# EEG_64.net
KiCad netlist of a schematic drawn in EAGLE
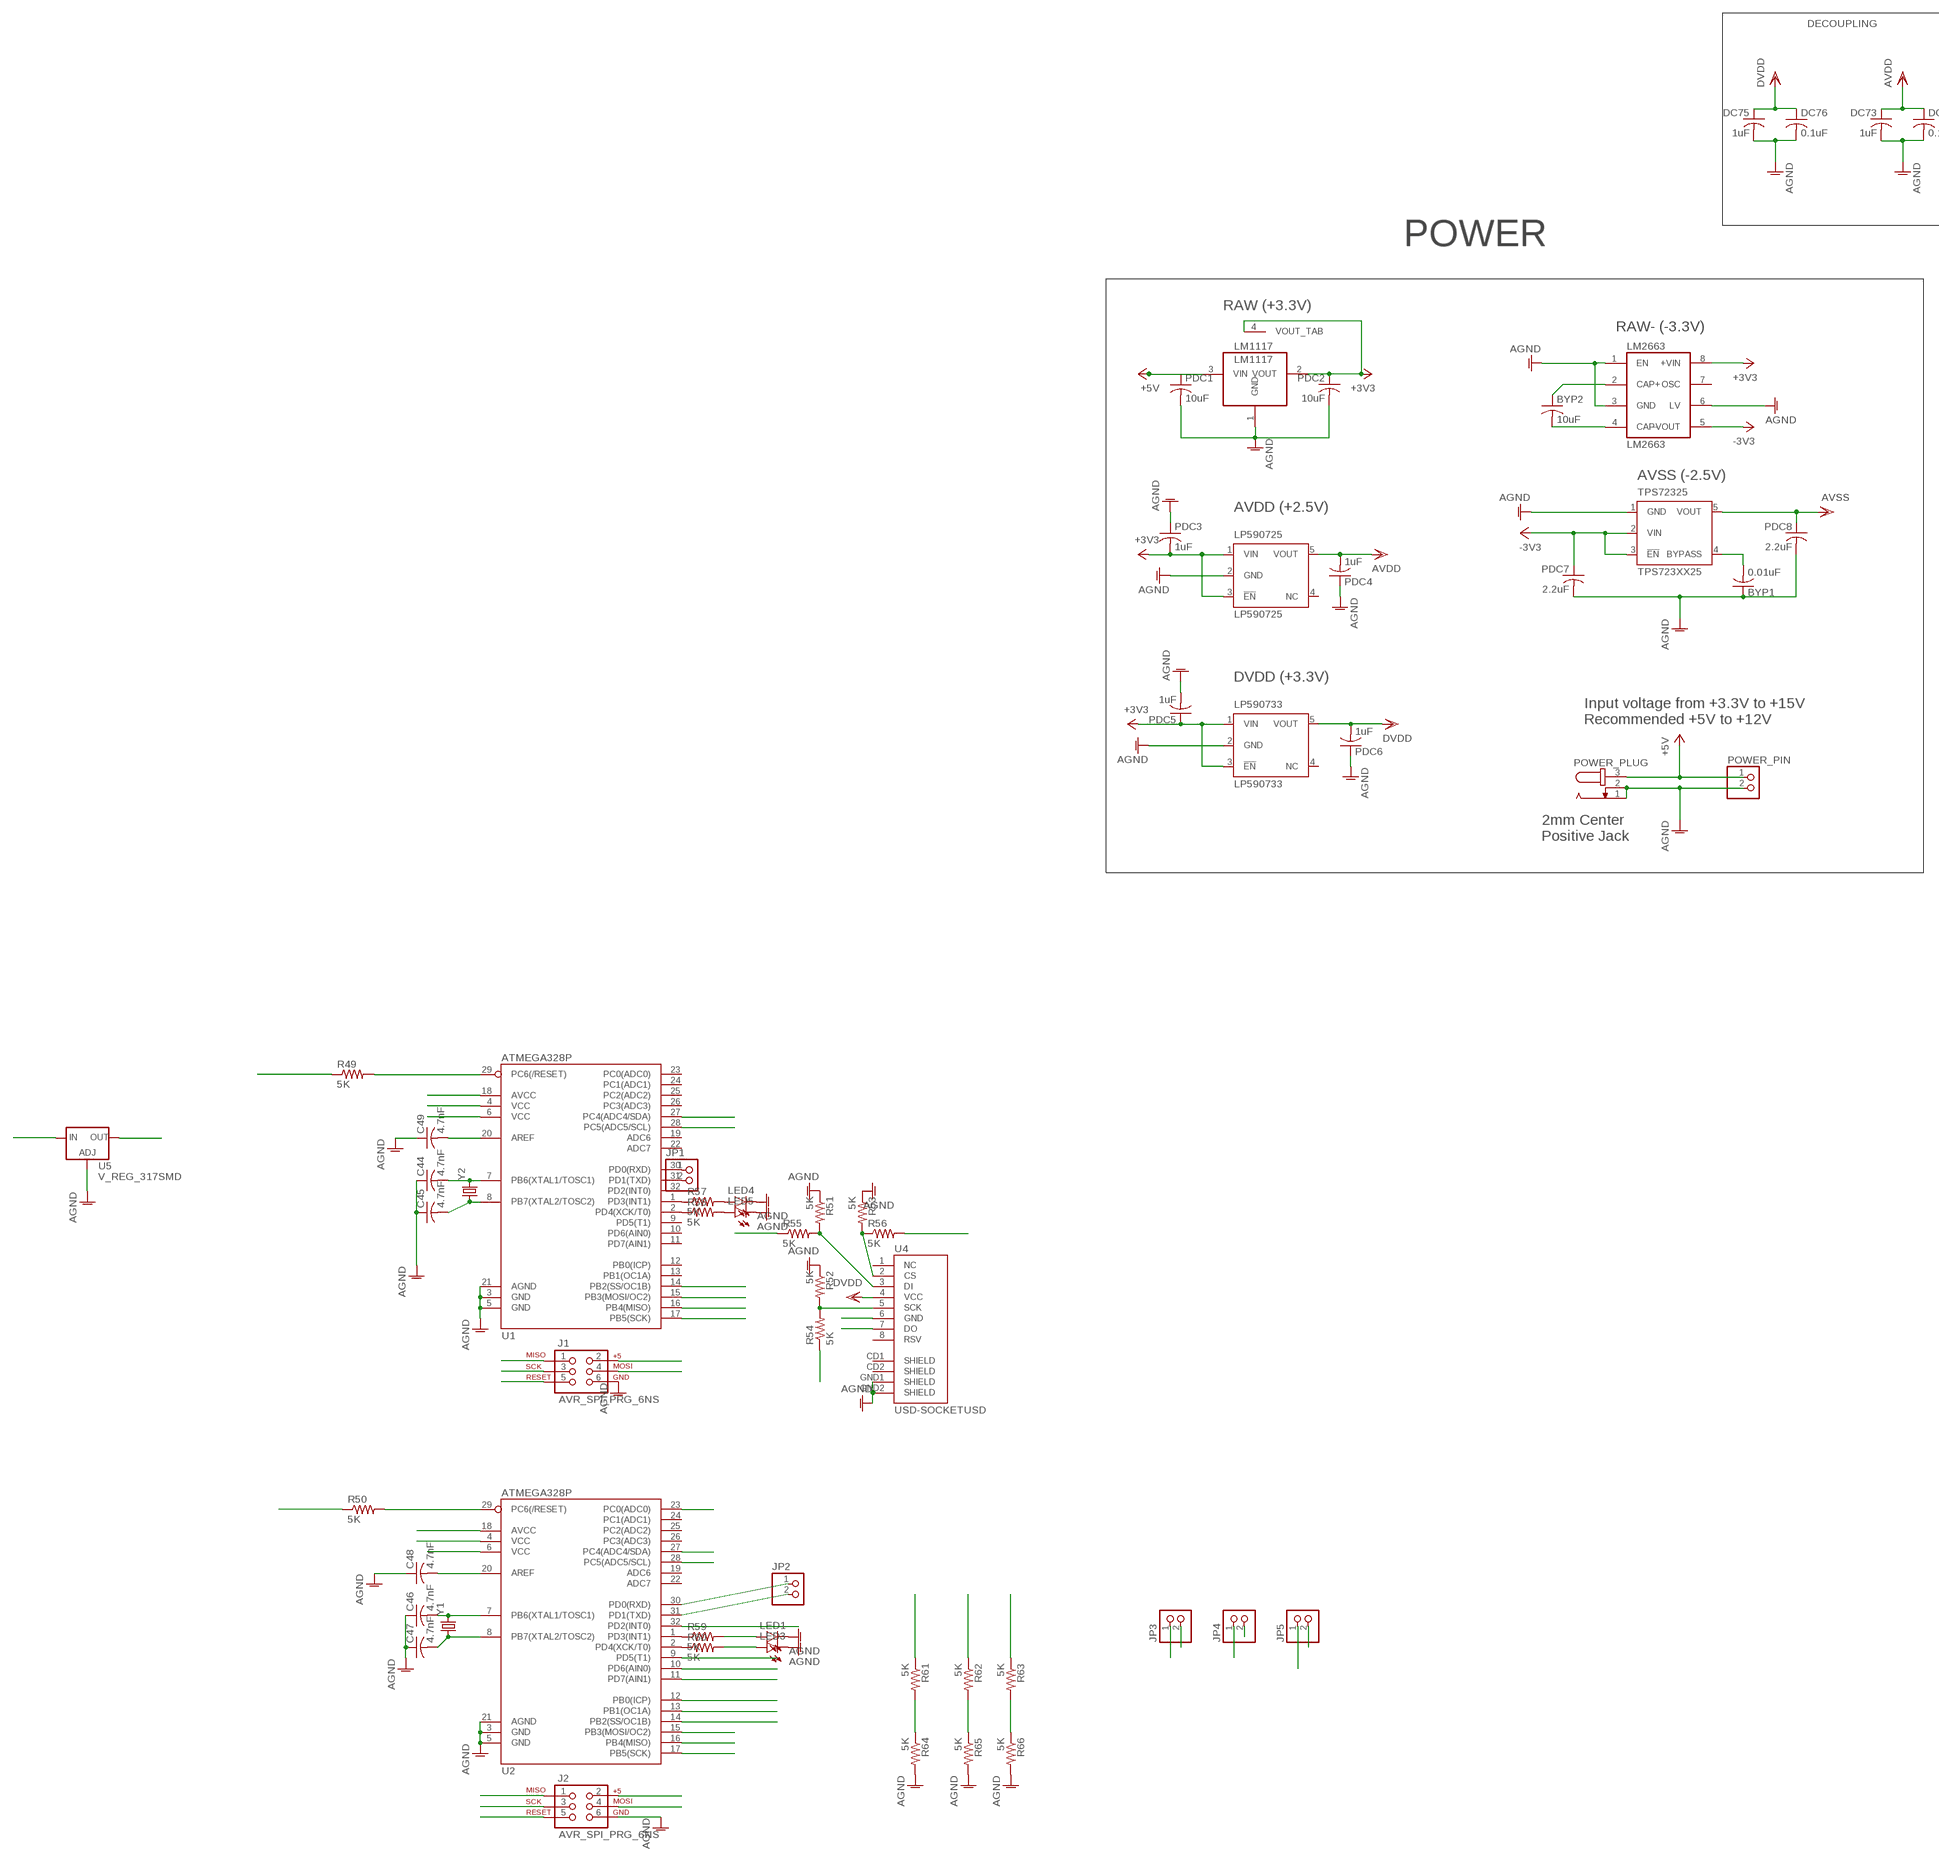
[diagram p0: schematic, sheet 1, part 1 of 3]
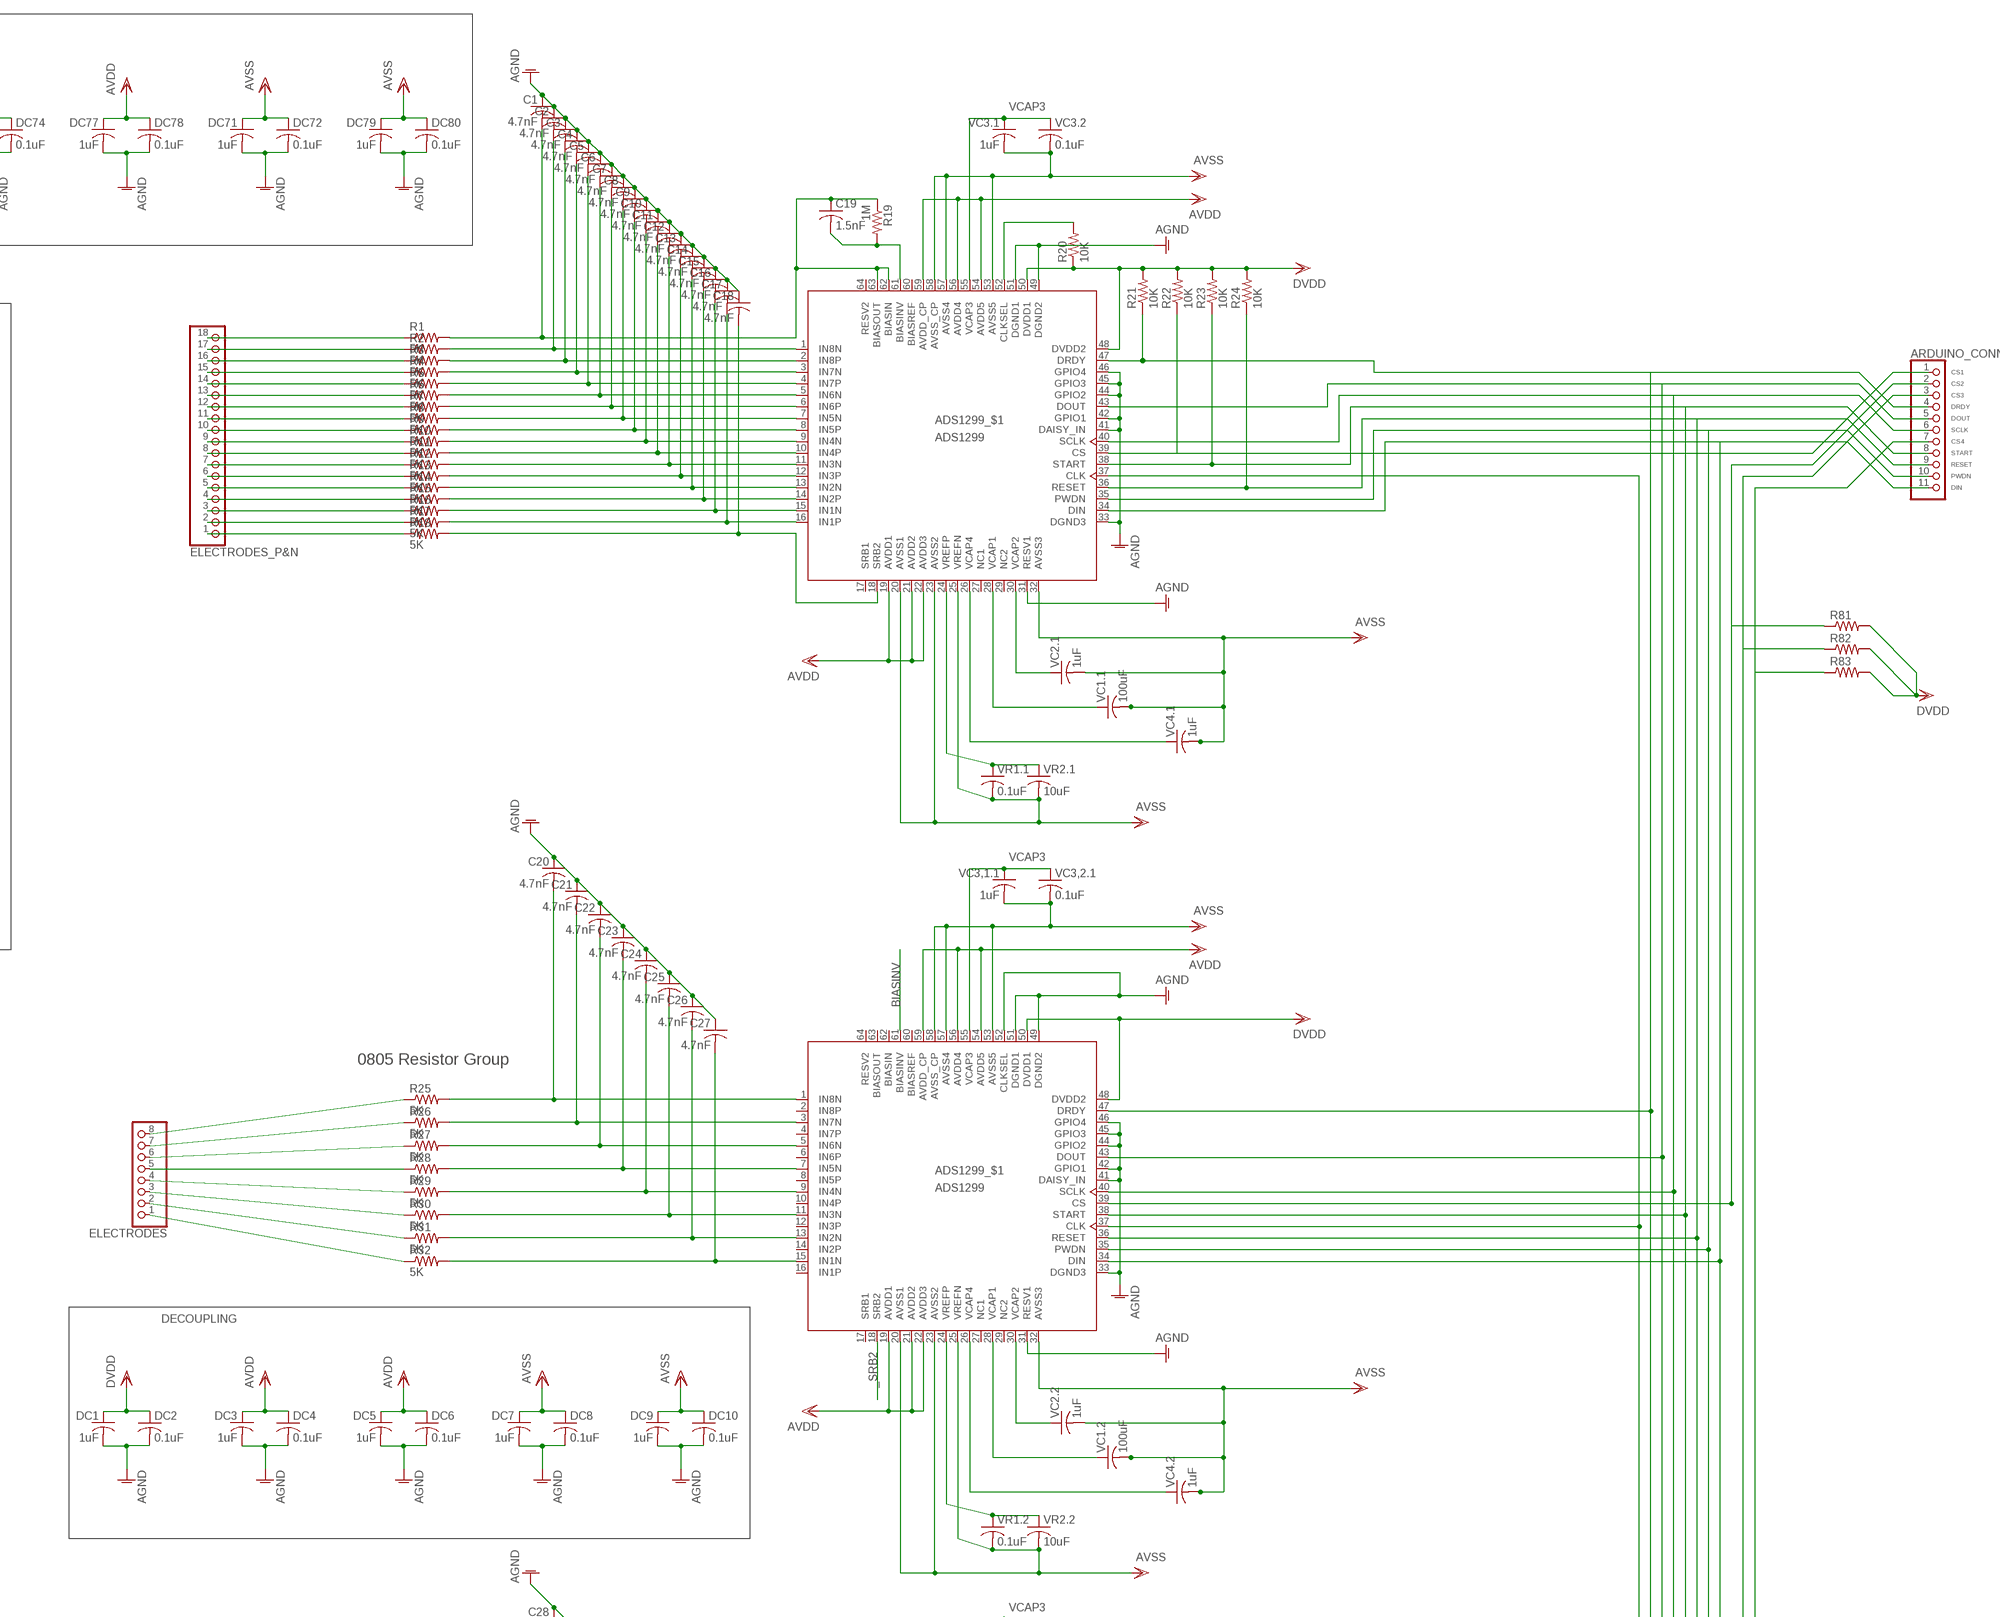
[diagram p1: schematic, sheet 1, part 2 of 3]
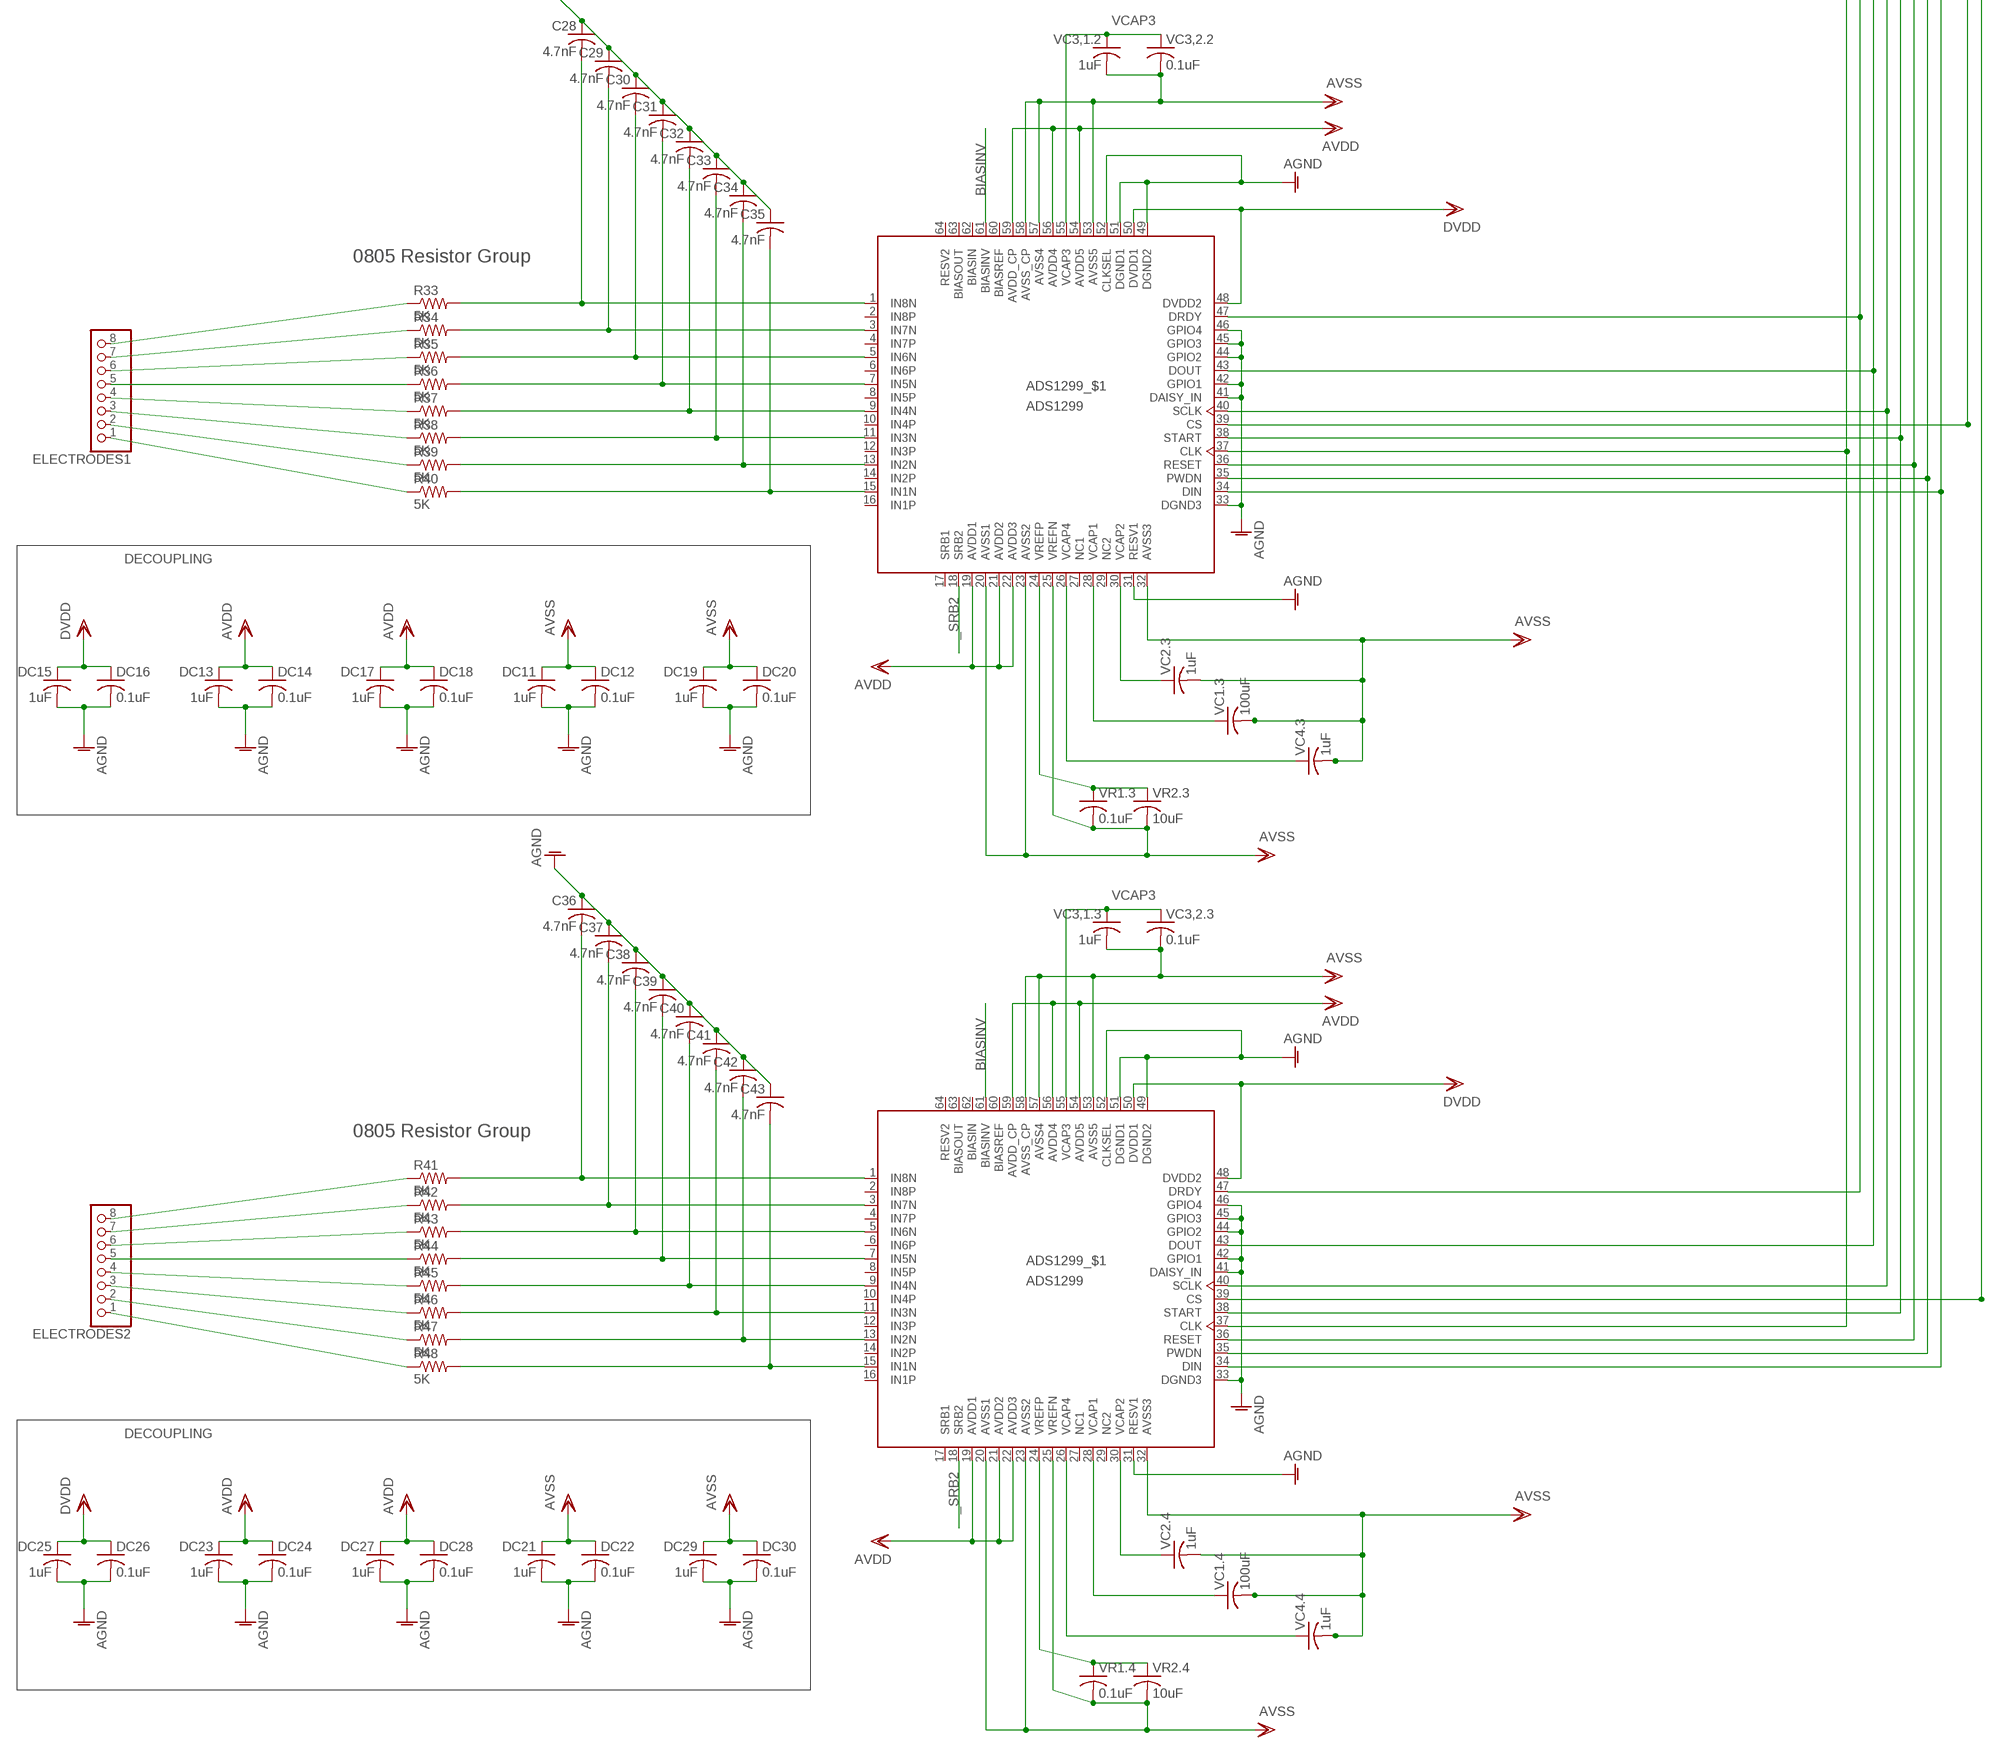
[diagram p2: schematic, sheet 1, part 3 of 3]

(export (version "E")
  (design (tool "Eeschema 10.0.6"))
  (components
    (comp (ref "ADS1")
      (value "ADS1299")
      (footprint "eagle-import:PAG_S-PQFP-G64")
      (fields (field (name "MF") "TEXAS INSTRUMENTS") (field (name "MPN") "ADS1299PAGR"))
      (libsource (lib "eagle-import") (part "ADS1299"))
    )
    (comp (ref "ADS2")
      (value "ADS1299")
      (footprint "eagle-import:PAG_S-PQFP-G64")
      (fields (field (name "MF") "TEXAS INSTRUMENTS") (field (name "MPN") "ADS1299PAGR"))
      (libsource (lib "eagle-import") (part "ADS1299"))
    )
    (comp (ref "ADS3")
      (value "ADS1299")
      (footprint "eagle-import:PAG_S-PQFP-G64")
      (fields (field (name "MF") "TEXAS INSTRUMENTS") (field (name "MPN") "ADS1299PAGR"))
      (libsource (lib "eagle-import") (part "ADS1299"))
    )
    (comp (ref "ADS4")
      (value "ADS1299")
      (footprint "eagle-import:PAG_S-PQFP-G64")
      (fields (field (name "MF") "TEXAS INSTRUMENTS") (field (name "MPN") "ADS1299PAGR"))
      (libsource (lib "eagle-import") (part "ADS1299"))
    )
    (comp (ref "ARDUINO_CONN")
      (value "PINHD-1X11")
      (footprint "eagle-import:1X11")
      (libsource (lib "eagle-import") (part "PINHD-1X11"))
    )
    (comp (ref "BYP1")
      (value "0.01uF")
      (footprint "eagle-import:C0603")
      (libsource (lib "eagle-import") (part "resistor_C-USC0603"))
    )
    (comp (ref "BYP2")
      (value "10uF")
      (footprint "eagle-import:C0603")
      (libsource (lib "eagle-import") (part "resistor_C-USC0603"))
    )
    (comp (ref "C1")
      (value "4.7nF")
      (footprint "eagle-import:C0603")
      (libsource (lib "eagle-import") (part "resistor_C-USC0603"))
    )
    (comp (ref "C2")
      (value "4.7nF")
      (footprint "eagle-import:C0603")
      (libsource (lib "eagle-import") (part "resistor_C-USC0603"))
    )
    (comp (ref "C3")
      (value "4.7nF")
      (footprint "eagle-import:C0603")
      (libsource (lib "eagle-import") (part "resistor_C-USC0603"))
    )
    (comp (ref "C4")
      (value "4.7nF")
      (footprint "eagle-import:C0603")
      (libsource (lib "eagle-import") (part "resistor_C-USC0603"))
    )
    (comp (ref "C5")
      (value "4.7nF")
      (footprint "eagle-import:C0603")
      (libsource (lib "eagle-import") (part "resistor_C-USC0603"))
    )
    (comp (ref "C6")
      (value "4.7nF")
      (footprint "eagle-import:C0603")
      (libsource (lib "eagle-import") (part "resistor_C-USC0603"))
    )
    (comp (ref "C7")
      (value "4.7nF")
      (footprint "eagle-import:C0603")
      (libsource (lib "eagle-import") (part "resistor_C-USC0603"))
    )
    (comp (ref "C8")
      (value "4.7nF")
      (footprint "eagle-import:C0603")
      (libsource (lib "eagle-import") (part "resistor_C-USC0603"))
    )
    (comp (ref "C9")
      (value "4.7nF")
      (footprint "eagle-import:C0603")
      (libsource (lib "eagle-import") (part "resistor_C-USC0603"))
    )
    (comp (ref "C10")
      (value "4.7nF")
      (footprint "eagle-import:C0603")
      (libsource (lib "eagle-import") (part "resistor_C-USC0603"))
    )
    (comp (ref "C11")
      (value "4.7nF")
      (footprint "eagle-import:C0603")
      (libsource (lib "eagle-import") (part "resistor_C-USC0603"))
    )
    (comp (ref "C12")
      (value "4.7nF")
      (footprint "eagle-import:C0603")
      (libsource (lib "eagle-import") (part "resistor_C-USC0603"))
    )
    (comp (ref "C13")
      (value "4.7nF")
      (footprint "eagle-import:C0603")
      (libsource (lib "eagle-import") (part "resistor_C-USC0603"))
    )
    (comp (ref "C14")
      (value "4.7nF")
      (footprint "eagle-import:C0603")
      (libsource (lib "eagle-import") (part "resistor_C-USC0603"))
    )
    (comp (ref "C15")
      (value "4.7nF")
      (footprint "eagle-import:C0603")
      (libsource (lib "eagle-import") (part "resistor_C-USC0603"))
    )
    (comp (ref "C16")
      (value "4.7nF")
      (footprint "eagle-import:C0603")
      (libsource (lib "eagle-import") (part "resistor_C-USC0603"))
    )
    (comp (ref "C17")
      (value "4.7nF")
      (footprint "eagle-import:C0603")
      (libsource (lib "eagle-import") (part "resistor_C-USC0603"))
    )
    (comp (ref "C18")
      (value "4.7nF")
      (footprint "eagle-import:C0603")
      (libsource (lib "eagle-import") (part "resistor_C-USC0603"))
    )
    (comp (ref "C19")
      (value "1.5nF")
      (footprint "eagle-import:C0603")
      (libsource (lib "eagle-import") (part "resistor_C-USC0603"))
    )
    (comp (ref "C20")
      (value "4.7nF")
      (footprint "eagle-import:C0603")
      (libsource (lib "eagle-import") (part "C-USC0603"))
    )
    (comp (ref "C21")
      (value "4.7nF")
      (footprint "eagle-import:C0603")
      (libsource (lib "eagle-import") (part "C-USC0603"))
    )
    (comp (ref "C22")
      (value "4.7nF")
      (footprint "eagle-import:C0603")
      (libsource (lib "eagle-import") (part "C-USC0603"))
    )
    (comp (ref "C23")
      (value "4.7nF")
      (footprint "eagle-import:C0603")
      (libsource (lib "eagle-import") (part "C-USC0603"))
    )
    (comp (ref "C24")
      (value "4.7nF")
      (footprint "eagle-import:C0603")
      (libsource (lib "eagle-import") (part "C-USC0603"))
    )
    (comp (ref "C25")
      (value "4.7nF")
      (footprint "eagle-import:C0603")
      (libsource (lib "eagle-import") (part "C-USC0603"))
    )
    (comp (ref "C26")
      (value "4.7nF")
      (footprint "eagle-import:C0603")
      (libsource (lib "eagle-import") (part "C-USC0603"))
    )
    (comp (ref "C27")
      (value "4.7nF")
      (footprint "eagle-import:C0603")
      (libsource (lib "eagle-import") (part "C-USC0603"))
    )
    (comp (ref "C28")
      (value "4.7nF")
      (footprint "eagle-import:C0603")
      (libsource (lib "eagle-import") (part "C-USC0603"))
    )
    (comp (ref "C29")
      (value "4.7nF")
      (footprint "eagle-import:C0603")
      (libsource (lib "eagle-import") (part "C-USC0603"))
    )
    (comp (ref "C30")
      (value "4.7nF")
      (footprint "eagle-import:C0603")
      (libsource (lib "eagle-import") (part "C-USC0603"))
    )
    (comp (ref "C31")
      (value "4.7nF")
      (footprint "eagle-import:C0603")
      (libsource (lib "eagle-import") (part "C-USC0603"))
    )
    (comp (ref "C32")
      (value "4.7nF")
      (footprint "eagle-import:C0603")
      (libsource (lib "eagle-import") (part "C-USC0603"))
    )
    (comp (ref "C33")
      (value "4.7nF")
      (footprint "eagle-import:C0603")
      (libsource (lib "eagle-import") (part "C-USC0603"))
    )
    (comp (ref "C34")
      (value "4.7nF")
      (footprint "eagle-import:C0603")
      (libsource (lib "eagle-import") (part "C-USC0603"))
    )
    (comp (ref "C35")
      (value "4.7nF")
      (footprint "eagle-import:C0603")
      (libsource (lib "eagle-import") (part "C-USC0603"))
    )
    (comp (ref "C36")
      (value "4.7nF")
      (footprint "eagle-import:C0603")
      (libsource (lib "eagle-import") (part "C-USC0603"))
    )
    (comp (ref "C37")
      (value "4.7nF")
      (footprint "eagle-import:C0603")
      (libsource (lib "eagle-import") (part "C-USC0603"))
    )
    (comp (ref "C38")
      (value "4.7nF")
      (footprint "eagle-import:C0603")
      (libsource (lib "eagle-import") (part "C-USC0603"))
    )
    (comp (ref "C39")
      (value "4.7nF")
      (footprint "eagle-import:C0603")
      (libsource (lib "eagle-import") (part "C-USC0603"))
    )
    (comp (ref "C40")
      (value "4.7nF")
      (footprint "eagle-import:C0603")
      (libsource (lib "eagle-import") (part "C-USC0603"))
    )
    (comp (ref "C41")
      (value "4.7nF")
      (footprint "eagle-import:C0603")
      (libsource (lib "eagle-import") (part "C-USC0603"))
    )
    (comp (ref "C42")
      (value "4.7nF")
      (footprint "eagle-import:C0603")
      (libsource (lib "eagle-import") (part "C-USC0603"))
    )
    (comp (ref "C43")
      (value "4.7nF")
      (footprint "eagle-import:C0603")
      (libsource (lib "eagle-import") (part "C-USC0603"))
    )
    (comp (ref "C44")
      (value "4.7nF")
      (footprint "eagle-import:C0603")
      (libsource (lib "eagle-import") (part "C-USC0603"))
    )
    (comp (ref "C45")
      (value "4.7nF")
      (footprint "eagle-import:C0603")
      (libsource (lib "eagle-import") (part "C-USC0603"))
    )
    (comp (ref "C46")
      (value "4.7nF")
      (footprint "eagle-import:C0603")
      (libsource (lib "eagle-import") (part "C-USC0603"))
    )
    (comp (ref "C47")
      (value "4.7nF")
      (footprint "eagle-import:C0603")
      (libsource (lib "eagle-import") (part "C-USC0603"))
    )
    (comp (ref "C48")
      (value "4.7nF")
      (footprint "eagle-import:C0603")
      (libsource (lib "eagle-import") (part "C-USC0603"))
    )
    (comp (ref "C49")
      (value "4.7nF")
      (footprint "eagle-import:C0603")
      (libsource (lib "eagle-import") (part "C-USC0603"))
    )
    (comp (ref "DC1")
      (value "1uF")
      (footprint "eagle-import:C0603")
      (libsource (lib "eagle-import") (part "C-USC0603"))
    )
    (comp (ref "DC2")
      (value "0.1uF")
      (footprint "eagle-import:C0603")
      (libsource (lib "eagle-import") (part "C-USC0603"))
    )
    (comp (ref "DC3")
      (value "1uF")
      (footprint "eagle-import:C0603")
      (libsource (lib "eagle-import") (part "C-USC0603"))
    )
    (comp (ref "DC4")
      (value "0.1uF")
      (footprint "eagle-import:C0603")
      (libsource (lib "eagle-import") (part "C-USC0603"))
    )
    (comp (ref "DC5")
      (value "1uF")
      (footprint "eagle-import:C0603")
      (libsource (lib "eagle-import") (part "C-USC0603"))
    )
    (comp (ref "DC6")
      (value "0.1uF")
      (footprint "eagle-import:C0603")
      (libsource (lib "eagle-import") (part "C-USC0603"))
    )
    (comp (ref "DC7")
      (value "1uF")
      (footprint "eagle-import:C0603")
      (libsource (lib "eagle-import") (part "C-USC0603"))
    )
    (comp (ref "DC8")
      (value "0.1uF")
      (footprint "eagle-import:C0603")
      (libsource (lib "eagle-import") (part "C-USC0603"))
    )
    (comp (ref "DC9")
      (value "1uF")
      (footprint "eagle-import:C0603")
      (libsource (lib "eagle-import") (part "C-USC0603"))
    )
    (comp (ref "DC10")
      (value "0.1uF")
      (footprint "eagle-import:C0603")
      (libsource (lib "eagle-import") (part "C-USC0603"))
    )
    (comp (ref "DC11")
      (value "1uF")
      (footprint "eagle-import:C0603")
      (libsource (lib "eagle-import") (part "C-USC0603"))
    )
    (comp (ref "DC12")
      (value "0.1uF")
      (footprint "eagle-import:C0603")
      (libsource (lib "eagle-import") (part "C-USC0603"))
    )
    (comp (ref "DC13")
      (value "1uF")
      (footprint "eagle-import:C0603")
      (libsource (lib "eagle-import") (part "C-USC0603"))
    )
    (comp (ref "DC14")
      (value "0.1uF")
      (footprint "eagle-import:C0603")
      (libsource (lib "eagle-import") (part "C-USC0603"))
    )
    (comp (ref "DC15")
      (value "1uF")
      (footprint "eagle-import:C0603")
      (libsource (lib "eagle-import") (part "C-USC0603"))
    )
    (comp (ref "DC16")
      (value "0.1uF")
      (footprint "eagle-import:C0603")
      (libsource (lib "eagle-import") (part "C-USC0603"))
    )
    (comp (ref "DC17")
      (value "1uF")
      (footprint "eagle-import:C0603")
      (libsource (lib "eagle-import") (part "C-USC0603"))
    )
    (comp (ref "DC18")
      (value "0.1uF")
      (footprint "eagle-import:C0603")
      (libsource (lib "eagle-import") (part "C-USC0603"))
    )
    (comp (ref "DC19")
      (value "1uF")
      (footprint "eagle-import:C0603")
      (libsource (lib "eagle-import") (part "C-USC0603"))
    )
    (comp (ref "DC20")
      (value "0.1uF")
      (footprint "eagle-import:C0603")
      (libsource (lib "eagle-import") (part "C-USC0603"))
    )
    (comp (ref "DC21")
      (value "1uF")
      (footprint "eagle-import:C0603")
      (libsource (lib "eagle-import") (part "C-USC0603"))
    )
    (comp (ref "DC22")
      (value "0.1uF")
      (footprint "eagle-import:C0603")
      (libsource (lib "eagle-import") (part "C-USC0603"))
    )
    (comp (ref "DC23")
      (value "1uF")
      (footprint "eagle-import:C0603")
      (libsource (lib "eagle-import") (part "C-USC0603"))
    )
    (comp (ref "DC24")
      (value "0.1uF")
      (footprint "eagle-import:C0603")
      (libsource (lib "eagle-import") (part "C-USC0603"))
    )
    (comp (ref "DC25")
      (value "1uF")
      (footprint "eagle-import:C0603")
      (libsource (lib "eagle-import") (part "C-USC0603"))
    )
    (comp (ref "DC26")
      (value "0.1uF")
      (footprint "eagle-import:C0603")
      (libsource (lib "eagle-import") (part "C-USC0603"))
    )
    (comp (ref "DC27")
      (value "1uF")
      (footprint "eagle-import:C0603")
      (libsource (lib "eagle-import") (part "C-USC0603"))
    )
    (comp (ref "DC28")
      (value "0.1uF")
      (footprint "eagle-import:C0603")
      (libsource (lib "eagle-import") (part "C-USC0603"))
    )
    (comp (ref "DC29")
      (value "1uF")
      (footprint "eagle-import:C0603")
      (libsource (lib "eagle-import") (part "C-USC0603"))
    )
    (comp (ref "DC30")
      (value "0.1uF")
      (footprint "eagle-import:C0603")
      (libsource (lib "eagle-import") (part "C-USC0603"))
    )
    (comp (ref "DC71")
      (value "1uF")
      (footprint "eagle-import:C0603")
      (libsource (lib "eagle-import") (part "C-USC0603"))
    )
    (comp (ref "DC72")
      (value "0.1uF")
      (footprint "eagle-import:C0603")
      (libsource (lib "eagle-import") (part "C-USC0603"))
    )
    (comp (ref "DC73")
      (value "1uF")
      (footprint "eagle-import:C0603")
      (libsource (lib "eagle-import") (part "C-USC0603"))
    )
    (comp (ref "DC74")
      (value "0.1uF")
      (footprint "eagle-import:C0603")
      (libsource (lib "eagle-import") (part "C-USC0603"))
    )
    (comp (ref "DC75")
      (value "1uF")
      (footprint "eagle-import:C0603")
      (libsource (lib "eagle-import") (part "C-USC0603"))
    )
    (comp (ref "DC76")
      (value "0.1uF")
      (footprint "eagle-import:C0603")
      (libsource (lib "eagle-import") (part "C-USC0603"))
    )
    (comp (ref "DC77")
      (value "1uF")
      (footprint "eagle-import:C0603")
      (libsource (lib "eagle-import") (part "C-USC0603"))
    )
    (comp (ref "DC78")
      (value "0.1uF")
      (footprint "eagle-import:C0603")
      (libsource (lib "eagle-import") (part "C-USC0603"))
    )
    (comp (ref "DC79")
      (value "1uF")
      (footprint "eagle-import:C0603")
      (libsource (lib "eagle-import") (part "C-USC0603"))
    )
    (comp (ref "DC80")
      (value "0.1uF")
      (footprint "eagle-import:C0603")
      (libsource (lib "eagle-import") (part "C-USC0603"))
    )
    (comp (ref "ELECTRODES")
      (value "PINHD-1X8")
      (footprint "eagle-import:1X08")
      (libsource (lib "eagle-import") (part "PINHD-1X8"))
    )
    (comp (ref "ELECTRODES1")
      (value "PINHD-1X8")
      (footprint "eagle-import:1X08")
      (libsource (lib "eagle-import") (part "PINHD-1X8"))
    )
    (comp (ref "ELECTRODES2")
      (value "PINHD-1X8")
      (footprint "eagle-import:1X08")
      (libsource (lib "eagle-import") (part "PINHD-1X8"))
    )
    (comp (ref "ELECTRODES_P&N")
      (value "PINHD-1X18")
      (footprint "eagle-import:1X18")
      (libsource (lib "eagle-import") (part "PINHD-1X18"))
    )
    (comp (ref "J1")
      (value "AVR_SPI_PRG_6NS")
      (footprint "eagle-import:2X3-NS")
      (libsource (lib "eagle-import") (part "AVR_SPI_PRG_6NS"))
    )
    (comp (ref "J2")
      (value "AVR_SPI_PRG_6NS")
      (footprint "eagle-import:2X3-NS")
      (libsource (lib "eagle-import") (part "AVR_SPI_PRG_6NS"))
    )
    (comp (ref "JP1")
      (value "PINHD-1X2")
      (footprint "eagle-import:1X02")
      (libsource (lib "eagle-import") (part "PINHD-1X2"))
    )
    (comp (ref "JP2")
      (value "PINHD-1X2")
      (footprint "eagle-import:1X02")
      (libsource (lib "eagle-import") (part "PINHD-1X2"))
    )
    (comp (ref "JP3")
      (value "PINHD-1X2")
      (footprint "eagle-import:1X02")
      (libsource (lib "eagle-import") (part "PINHD-1X2"))
    )
    (comp (ref "JP4")
      (value "PINHD-1X2")
      (footprint "eagle-import:1X02")
      (libsource (lib "eagle-import") (part "PINHD-1X2"))
    )
    (comp (ref "JP5")
      (value "PINHD-1X2")
      (footprint "eagle-import:1X02")
      (libsource (lib "eagle-import") (part "PINHD-1X2"))
    )
    (comp (ref "LED1")
      (value "LED0603")
      (footprint "eagle-import:LED-0603")
      (libsource (lib "eagle-import") (part "LED0603"))
    )
    (comp (ref "LED3")
      (value "LED0603")
      (footprint "eagle-import:LED-0603")
      (libsource (lib "eagle-import") (part "LED0603"))
    )
    (comp (ref "LED4")
      (value "LED0603")
      (footprint "eagle-import:LED-0603")
      (libsource (lib "eagle-import") (part "LED0603"))
    )
    (comp (ref "LED5")
      (value "LED0603")
      (footprint "eagle-import:LED-0603")
      (libsource (lib "eagle-import") (part "LED0603"))
    )
    (comp (ref "LM1117")
      (value "LM1117")
      (footprint "eagle-import:SOT223")
      (fields (field (name "MPN") "REG1117"))
      (libsource (lib "eagle-import") (part "LM1117"))
    )
    (comp (ref "LM2663")
      (value "LM2663")
      (footprint "eagle-import:SO-08")
      (libsource (lib "eagle-import") (part "LM2663"))
    )
    (comp (ref "LP590725")
      (value "LP590725")
      (footprint "eagle-import:SOT23-DBV")
      (fields (field (name "MF") "TEXAS INSTRUMENTS") (field (name "MPN") "TPS77025DBVR"))
      (libsource (lib "eagle-import") (part "LP590725"))
    )
    (comp (ref "LP590733")
      (value "LP590733")
      (footprint "eagle-import:SOT23-DBV")
      (fields (field (name "MF") "TEXAS INSTRUMENTS") (field (name "MPN") "TPS77033DBVT"))
      (libsource (lib "eagle-import") (part "LP590733"))
    )
    (comp (ref "PDC1")
      (value "10uF")
      (footprint "eagle-import:C0603")
      (libsource (lib "eagle-import") (part "resistor_C-USC0603"))
    )
    (comp (ref "PDC2")
      (value "10uF")
      (footprint "eagle-import:C0603")
      (libsource (lib "eagle-import") (part "resistor_C-USC0603"))
    )
    (comp (ref "PDC3")
      (value "1uF")
      (footprint "eagle-import:C0603")
      (libsource (lib "eagle-import") (part "resistor_C-USC0603"))
    )
    (comp (ref "PDC4")
      (value "1uF")
      (footprint "eagle-import:C0603")
      (libsource (lib "eagle-import") (part "resistor_C-USC0603"))
    )
    (comp (ref "PDC5")
      (value "1uF")
      (footprint "eagle-import:C0603")
      (libsource (lib "eagle-import") (part "resistor_C-USC0603"))
    )
    (comp (ref "PDC6")
      (value "1uF")
      (footprint "eagle-import:C0603")
      (libsource (lib "eagle-import") (part "resistor_C-USC0603"))
    )
    (comp (ref "PDC7")
      (value "2.2uF")
      (footprint "eagle-import:C0603")
      (libsource (lib "eagle-import") (part "resistor_C-USC0603"))
    )
    (comp (ref "PDC8")
      (value "2.2uF")
      (footprint "eagle-import:C0603")
      (libsource (lib "eagle-import") (part "resistor_C-USC0603"))
    )
    (comp (ref "POWER_PIN")
      (value "PINHD-1X2")
      (footprint "eagle-import:1X02")
      (libsource (lib "eagle-import") (part "PINHD-1X2"))
    )
    (comp (ref "POWER_PLUG")
      (value "JACK-PLUG0")
      (footprint "eagle-import:SPC4077")
      (libsource (lib "eagle-import") (part "JACK-PLUG0"))
    )
    (comp (ref "R1")
      (value "5K")
      (footprint "eagle-import:R0603")
      (libsource (lib "eagle-import") (part "resistor_R-US_R0603"))
    )
    (comp (ref "R2")
      (value "5K")
      (footprint "eagle-import:R0603")
      (libsource (lib "eagle-import") (part "resistor_R-US_R0603"))
    )
    (comp (ref "R3")
      (value "5K")
      (footprint "eagle-import:R0603")
      (libsource (lib "eagle-import") (part "resistor_R-US_R0603"))
    )
    (comp (ref "R4")
      (value "5K")
      (footprint "eagle-import:R0603")
      (libsource (lib "eagle-import") (part "resistor_R-US_R0603"))
    )
    (comp (ref "R5")
      (value "5K")
      (footprint "eagle-import:R0603")
      (libsource (lib "eagle-import") (part "resistor_R-US_R0603"))
    )
    (comp (ref "R6")
      (value "5K")
      (footprint "eagle-import:R0603")
      (libsource (lib "eagle-import") (part "resistor_R-US_R0603"))
    )
    (comp (ref "R7")
      (value "5K")
      (footprint "eagle-import:R0603")
      (libsource (lib "eagle-import") (part "resistor_R-US_R0603"))
    )
    (comp (ref "R8")
      (value "5K")
      (footprint "eagle-import:R0603")
      (libsource (lib "eagle-import") (part "resistor_R-US_R0603"))
    )
    (comp (ref "R9")
      (value "5K")
      (footprint "eagle-import:R0603")
      (libsource (lib "eagle-import") (part "resistor_R-US_R0603"))
    )
    (comp (ref "R10")
      (value "5K")
      (footprint "eagle-import:R0603")
      (libsource (lib "eagle-import") (part "resistor_R-US_R0603"))
    )
    (comp (ref "R11")
      (value "5K")
      (footprint "eagle-import:R0603")
      (libsource (lib "eagle-import") (part "resistor_R-US_R0603"))
    )
    (comp (ref "R12")
      (value "5K")
      (footprint "eagle-import:R0603")
      (libsource (lib "eagle-import") (part "resistor_R-US_R0603"))
    )
    (comp (ref "R13")
      (value "5K")
      (footprint "eagle-import:R0603")
      (libsource (lib "eagle-import") (part "resistor_R-US_R0603"))
    )
    (comp (ref "R14")
      (value "5K")
      (footprint "eagle-import:R0603")
      (libsource (lib "eagle-import") (part "resistor_R-US_R0603"))
    )
    (comp (ref "R15")
      (value "5K")
      (footprint "eagle-import:R0603")
      (libsource (lib "eagle-import") (part "resistor_R-US_R0603"))
    )
    (comp (ref "R16")
      (value "5K")
      (footprint "eagle-import:R0603")
      (libsource (lib "eagle-import") (part "resistor_R-US_R0603"))
    )
    (comp (ref "R17")
      (value "5K")
      (footprint "eagle-import:R0603")
      (libsource (lib "eagle-import") (part "resistor_R-US_R0603"))
    )
    (comp (ref "R18")
      (value "5K")
      (footprint "eagle-import:R0603")
      (libsource (lib "eagle-import") (part "resistor_R-US_R0603"))
    )
    (comp (ref "R19")
      (value "1M")
      (footprint "eagle-import:R0603")
      (libsource (lib "eagle-import") (part "resistor_R-US_R0603"))
    )
    (comp (ref "R20")
      (value "10K")
      (footprint "eagle-import:R0603")
      (libsource (lib "eagle-import") (part "resistor_R-US_R0603"))
    )
    (comp (ref "R21")
      (value "10K")
      (footprint "eagle-import:R0603")
      (libsource (lib "eagle-import") (part "resistor_R-US_R0603"))
    )
    (comp (ref "R22")
      (value "10K")
      (footprint "eagle-import:R0603")
      (libsource (lib "eagle-import") (part "resistor_R-US_R0603"))
    )
    (comp (ref "R23")
      (value "10K")
      (footprint "eagle-import:R0603")
      (libsource (lib "eagle-import") (part "resistor_R-US_R0603"))
    )
    (comp (ref "R24")
      (value "10K")
      (footprint "eagle-import:R0603")
      (libsource (lib "eagle-import") (part "resistor_R-US_R0603"))
    )
    (comp (ref "R25")
      (value "5K")
      (footprint "eagle-import:R0603")
      (libsource (lib "eagle-import") (part "R-US_R0603"))
    )
    (comp (ref "R26")
      (value "5K")
      (footprint "eagle-import:R0603")
      (libsource (lib "eagle-import") (part "R-US_R0603"))
    )
    (comp (ref "R27")
      (value "5K")
      (footprint "eagle-import:R0603")
      (libsource (lib "eagle-import") (part "R-US_R0603"))
    )
    (comp (ref "R28")
      (value "5K")
      (footprint "eagle-import:R0603")
      (libsource (lib "eagle-import") (part "R-US_R0603"))
    )
    (comp (ref "R29")
      (value "5K")
      (footprint "eagle-import:R0603")
      (libsource (lib "eagle-import") (part "R-US_R0603"))
    )
    (comp (ref "R30")
      (value "5K")
      (footprint "eagle-import:R0603")
      (libsource (lib "eagle-import") (part "R-US_R0603"))
    )
    (comp (ref "R31")
      (value "5K")
      (footprint "eagle-import:R0603")
      (libsource (lib "eagle-import") (part "R-US_R0603"))
    )
    (comp (ref "R32")
      (value "5K")
      (footprint "eagle-import:R0603")
      (libsource (lib "eagle-import") (part "R-US_R0603"))
    )
    (comp (ref "R33")
      (value "5K")
      (footprint "eagle-import:R0603")
      (libsource (lib "eagle-import") (part "R-US_R0603"))
    )
    (comp (ref "R34")
      (value "5K")
      (footprint "eagle-import:R0603")
      (libsource (lib "eagle-import") (part "R-US_R0603"))
    )
    (comp (ref "R35")
      (value "5K")
      (footprint "eagle-import:R0603")
      (libsource (lib "eagle-import") (part "R-US_R0603"))
    )
    (comp (ref "R36")
      (value "5K")
      (footprint "eagle-import:R0603")
      (libsource (lib "eagle-import") (part "R-US_R0603"))
    )
    (comp (ref "R37")
      (value "5K")
      (footprint "eagle-import:R0603")
      (libsource (lib "eagle-import") (part "R-US_R0603"))
    )
    (comp (ref "R38")
      (value "5K")
      (footprint "eagle-import:R0603")
      (libsource (lib "eagle-import") (part "R-US_R0603"))
    )
    (comp (ref "R39")
      (value "5K")
      (footprint "eagle-import:R0603")
      (libsource (lib "eagle-import") (part "R-US_R0603"))
    )
    (comp (ref "R40")
      (value "5K")
      (footprint "eagle-import:R0603")
      (libsource (lib "eagle-import") (part "R-US_R0603"))
    )
    (comp (ref "R41")
      (value "5K")
      (footprint "eagle-import:R0603")
      (libsource (lib "eagle-import") (part "R-US_R0603"))
    )
    (comp (ref "R42")
      (value "5K")
      (footprint "eagle-import:R0603")
      (libsource (lib "eagle-import") (part "R-US_R0603"))
    )
    (comp (ref "R43")
      (value "5K")
      (footprint "eagle-import:R0603")
      (libsource (lib "eagle-import") (part "R-US_R0603"))
    )
    (comp (ref "R44")
      (value "5K")
      (footprint "eagle-import:R0603")
      (libsource (lib "eagle-import") (part "R-US_R0603"))
    )
    (comp (ref "R45")
      (value "5K")
      (footprint "eagle-import:R0603")
      (libsource (lib "eagle-import") (part "R-US_R0603"))
    )
    (comp (ref "R46")
      (value "5K")
      (footprint "eagle-import:R0603")
      (libsource (lib "eagle-import") (part "R-US_R0603"))
    )
    (comp (ref "R47")
      (value "5K")
      (footprint "eagle-import:R0603")
      (libsource (lib "eagle-import") (part "R-US_R0603"))
    )
    (comp (ref "R48")
      (value "5K")
      (footprint "eagle-import:R0603")
      (libsource (lib "eagle-import") (part "R-US_R0603"))
    )
    (comp (ref "R49")
      (value "5K")
      (footprint "eagle-import:R0603")
      (libsource (lib "eagle-import") (part "R-US_R0603"))
    )
    (comp (ref "R50")
      (value "5K")
      (footprint "eagle-import:R0603")
      (libsource (lib "eagle-import") (part "R-US_R0603"))
    )
    (comp (ref "R51")
      (value "5K")
      (footprint "eagle-import:R0603")
      (libsource (lib "eagle-import") (part "R-US_R0603"))
    )
    (comp (ref "R52")
      (value "5K")
      (footprint "eagle-import:R0603")
      (libsource (lib "eagle-import") (part "R-US_R0603"))
    )
    (comp (ref "R53")
      (value "5K")
      (footprint "eagle-import:R0603")
      (libsource (lib "eagle-import") (part "R-US_R0603"))
    )
    (comp (ref "R54")
      (value "5K")
      (footprint "eagle-import:R0603")
      (libsource (lib "eagle-import") (part "R-US_R0603"))
    )
    (comp (ref "R55")
      (value "5K")
      (footprint "eagle-import:R0603")
      (libsource (lib "eagle-import") (part "R-US_R0603"))
    )
    (comp (ref "R56")
      (value "5K")
      (footprint "eagle-import:R0603")
      (libsource (lib "eagle-import") (part "R-US_R0603"))
    )
    (comp (ref "R57")
      (value "5K")
      (footprint "eagle-import:R0603")
      (libsource (lib "eagle-import") (part "R-US_R0603"))
    )
    (comp (ref "R58")
      (value "5K")
      (footprint "eagle-import:R0603")
      (libsource (lib "eagle-import") (part "R-US_R0603"))
    )
    (comp (ref "R59")
      (value "5K")
      (footprint "eagle-import:R0603")
      (libsource (lib "eagle-import") (part "R-US_R0603"))
    )
    (comp (ref "R60")
      (value "5K")
      (footprint "eagle-import:R0603")
      (libsource (lib "eagle-import") (part "R-US_R0603"))
    )
    (comp (ref "R61")
      (value "5K")
      (footprint "eagle-import:R0603")
      (libsource (lib "eagle-import") (part "R-US_R0603"))
    )
    (comp (ref "R62")
      (value "5K")
      (footprint "eagle-import:R0603")
      (libsource (lib "eagle-import") (part "R-US_R0603"))
    )
    (comp (ref "R63")
      (value "5K")
      (footprint "eagle-import:R0603")
      (libsource (lib "eagle-import") (part "R-US_R0603"))
    )
    (comp (ref "R64")
      (value "5K")
      (footprint "eagle-import:R0603")
      (libsource (lib "eagle-import") (part "R-US_R0603"))
    )
    (comp (ref "R65")
      (value "5K")
      (footprint "eagle-import:R0603")
      (libsource (lib "eagle-import") (part "R-US_R0603"))
    )
    (comp (ref "R66")
      (value "5K")
      (footprint "eagle-import:R0603")
      (libsource (lib "eagle-import") (part "R-US_R0603"))
    )
    (comp (ref "R81")
      (value "R-US_R0603")
      (footprint "eagle-import:R0603")
      (libsource (lib "eagle-import") (part "resistor_R-US_R0603"))
    )
    (comp (ref "R82")
      (value "R-US_R0603")
      (footprint "eagle-import:R0603")
      (libsource (lib "eagle-import") (part "resistor_R-US_R0603"))
    )
    (comp (ref "R83")
      (value "R-US_R0603")
      (footprint "eagle-import:R0603")
      (libsource (lib "eagle-import") (part "resistor_R-US_R0603"))
    )
    (comp (ref "TPS72325")
      (value "TPS723XX25")
      (footprint "eagle-import:SOT23-DBV")
      (fields (field (name "MF") "TEXAS INSTRUMENTS") (field (name "MPN") "TPS77025DBVR"))
      (libsource (lib "eagle-import") (part "TPS723XX25"))
    )
    (comp (ref "U1")
      (value "ATMEGA328P")
      (footprint "eagle-import:TQFP32-08")
      (libsource (lib "eagle-import") (part "ATMEGA328_SMT"))
    )
    (comp (ref "U2")
      (value "ATMEGA328P")
      (footprint "eagle-import:TQFP32-08")
      (libsource (lib "eagle-import") (part "ATMEGA328_SMT"))
    )
    (comp (ref "U4")
      (value "USD-SOCKETUSD")
      (footprint "eagle-import:USD-SOCKET-PP")
      (libsource (lib "eagle-import") (part "USD-SOCKETUSD"))
    )
    (comp (ref "U5")
      (value "V_REG_317SMD")
      (footprint "eagle-import:SOT223")
      (libsource (lib "eagle-import") (part "V_REG_317SMD"))
    )
    (comp (ref "VC1.1")
      (value "100uF")
      (footprint "eagle-import:C0603")
      (libsource (lib "eagle-import") (part "resistor_C-USC0603"))
    )
    (comp (ref "VC1.2")
      (value "100uF")
      (footprint "eagle-import:C0603")
      (libsource (lib "eagle-import") (part "C-USC0603"))
    )
    (comp (ref "VC1.3")
      (value "100uF")
      (footprint "eagle-import:C0603")
      (libsource (lib "eagle-import") (part "C-USC0603"))
    )
    (comp (ref "VC1.4")
      (value "100uF")
      (footprint "eagle-import:C0603")
      (libsource (lib "eagle-import") (part "C-USC0603"))
    )
    (comp (ref "VC2.1")
      (value "1uF")
      (footprint "eagle-import:C0603")
      (libsource (lib "eagle-import") (part "resistor_C-USC0603"))
    )
    (comp (ref "VC2.2")
      (value "1uF")
      (footprint "eagle-import:C0603")
      (libsource (lib "eagle-import") (part "C-USC0603"))
    )
    (comp (ref "VC2.3")
      (value "1uF")
      (footprint "eagle-import:C0603")
      (libsource (lib "eagle-import") (part "C-USC0603"))
    )
    (comp (ref "VC2.4")
      (value "1uF")
      (footprint "eagle-import:C0603")
      (libsource (lib "eagle-import") (part "C-USC0603"))
    )
    (comp (ref "VC3,1.1")
      (value "1uF")
      (footprint "eagle-import:C0603")
      (libsource (lib "eagle-import") (part "C-USC0603"))
    )
    (comp (ref "VC3,1.2")
      (value "1uF")
      (footprint "eagle-import:C0603")
      (libsource (lib "eagle-import") (part "C-USC0603"))
    )
    (comp (ref "VC3,1.3")
      (value "1uF")
      (footprint "eagle-import:C0603")
      (libsource (lib "eagle-import") (part "C-USC0603"))
    )
    (comp (ref "VC3,2.1")
      (value "0.1uF")
      (footprint "eagle-import:C0603")
      (libsource (lib "eagle-import") (part "C-USC0603"))
    )
    (comp (ref "VC3,2.2")
      (value "0.1uF")
      (footprint "eagle-import:C0603")
      (libsource (lib "eagle-import") (part "C-USC0603"))
    )
    (comp (ref "VC3,2.3")
      (value "0.1uF")
      (footprint "eagle-import:C0603")
      (libsource (lib "eagle-import") (part "C-USC0603"))
    )
    (comp (ref "VC3.1")
      (value "1uF")
      (footprint "eagle-import:C0603")
      (libsource (lib "eagle-import") (part "resistor_C-USC0603"))
    )
    (comp (ref "VC3.2")
      (value "0.1uF")
      (footprint "eagle-import:C0603")
      (libsource (lib "eagle-import") (part "resistor_C-USC0603"))
    )
    (comp (ref "VC4.1")
      (value "1uF")
      (footprint "eagle-import:C0603")
      (libsource (lib "eagle-import") (part "resistor_C-USC0603"))
    )
    (comp (ref "VC4.2")
      (value "1uF")
      (footprint "eagle-import:C0603")
      (libsource (lib "eagle-import") (part "C-USC0603"))
    )
    (comp (ref "VC4.3")
      (value "1uF")
      (footprint "eagle-import:C0603")
      (libsource (lib "eagle-import") (part "C-USC0603"))
    )
    (comp (ref "VC4.4")
      (value "1uF")
      (footprint "eagle-import:C0603")
      (libsource (lib "eagle-import") (part "C-USC0603"))
    )
    (comp (ref "VR1.1")
      (value "0.1uF")
      (footprint "eagle-import:C0603")
      (libsource (lib "eagle-import") (part "resistor_C-USC0603"))
    )
    (comp (ref "VR1.2")
      (value "0.1uF")
      (footprint "eagle-import:C0603")
      (libsource (lib "eagle-import") (part "C-USC0603"))
    )
    (comp (ref "VR1.3")
      (value "0.1uF")
      (footprint "eagle-import:C0603")
      (libsource (lib "eagle-import") (part "C-USC0603"))
    )
    (comp (ref "VR1.4")
      (value "0.1uF")
      (footprint "eagle-import:C0603")
      (libsource (lib "eagle-import") (part "C-USC0603"))
    )
    (comp (ref "VR2.1")
      (value "10uF")
      (footprint "eagle-import:C0603")
      (libsource (lib "eagle-import") (part "resistor_C-USC0603"))
    )
    (comp (ref "VR2.2")
      (value "10uF")
      (footprint "eagle-import:C0603")
      (libsource (lib "eagle-import") (part "C-USC0603"))
    )
    (comp (ref "VR2.3")
      (value "10uF")
      (footprint "eagle-import:C0603")
      (libsource (lib "eagle-import") (part "C-USC0603"))
    )
    (comp (ref "VR2.4")
      (value "10uF")
      (footprint "eagle-import:C0603")
      (libsource (lib "eagle-import") (part "C-USC0603"))
    )
    (comp (ref "Y1")
      (value "CRYSTAL5X3")
      (footprint "eagle-import:CRYSTAL-SMD-5X3")
      (libsource (lib "eagle-import") (part "CRYSTAL5X3"))
    )
    (comp (ref "Y2")
      (value "CRYSTAL5X3")
      (footprint "eagle-import:CRYSTAL-SMD-5X3")
      (libsource (lib "eagle-import") (part "CRYSTAL5X3"))
    )
  )
  (nets
    (net (code "1") (name "+3V3") (class "Default")
      (node (ref "LM1117") (pin "2") (pinfunction "VOUT_2") (pintype "power_in"))
      (node (ref "LM1117") (pin "4") (pinfunction "VOUT_TAB_4") (pintype "power_in"))
      (node (ref "LM2663") (pin "8") (pinfunction "+VIN_8") (pintype "power_in"))
      (node (ref "LP590725") (pin "1") (pinfunction "VIN_1") (pintype "power_in"))
      (node (ref "LP590725") (pin "3") (pinfunction "~{EN}_3") (pintype "input"))
      (node (ref "LP590733") (pin "1") (pinfunction "VIN_1") (pintype "power_in"))
      (node (ref "LP590733") (pin "3") (pinfunction "~{EN}_3") (pintype "input"))
      (node (ref "PDC2") (pin "1") (pinfunction "1_1") (pintype "passive"))
      (node (ref "PDC3") (pin "2") (pinfunction "2_2") (pintype "passive"))
      (node (ref "PDC5") (pin "1") (pinfunction "1_1") (pintype "passive"))
    )
    (net (code "2") (name "+5V") (class "Default")
      (node (ref "LM1117") (pin "3") (pinfunction "VIN_3") (pintype "power_in"))
      (node (ref "PDC1") (pin "1") (pinfunction "1_1") (pintype "passive"))
      (node (ref "POWER_PIN") (pin "1") (pinfunction "1_1") (pintype "passive"))
      (node (ref "POWER_PLUG") (pin "3") (pinfunction "3_3") (pintype "passive"))
      (node (ref "U5") (pin "3") (pinfunction "IN_3") (pintype "input"))
    )
    (net (code "3") (name "-3V3") (class "Default")
      (node (ref "LM2663") (pin "5") (pinfunction "-VOUT_5") (pintype "power_in"))
      (node (ref "PDC7") (pin "1") (pinfunction "1_1") (pintype "passive"))
      (node (ref "TPS72325") (pin "2") (pinfunction "VIN_2") (pintype "power_in"))
      (node (ref "TPS72325") (pin "3") (pinfunction "~{EN}_3") (pintype "input"))
    )
    (net (code "4") (name "/BIASINV") (class "Default")
      (node (ref "ADS1") (pin "61") (pinfunction "BIASINV_61") (pintype "bidirectional"))
      (node (ref "ADS2") (pin "61") (pinfunction "BIASINV_61") (pintype "bidirectional"))
      (node (ref "ADS3") (pin "61") (pinfunction "BIASINV_61") (pintype "bidirectional"))
      (node (ref "ADS4") (pin "61") (pinfunction "BIASINV_61") (pintype "bidirectional"))
      (node (ref "C19") (pin "2") (pinfunction "2_2") (pintype "passive"))
      (node (ref "R19") (pin "2") (pinfunction "2_2") (pintype "passive"))
    )
    (net (code "5") (name "/CLK") (class "Default")
      (node (ref "U1") (pin "28") (pinfunction "PC5(ADC5/SCL)_28") (pintype "bidirectional"))
      (node (ref "U2") (pin "28") (pinfunction "PC5(ADC5/SCL)_28") (pintype "bidirectional"))
    )
    (net (code "6") (name "/CS") (class "Default")
      (node (ref "R56") (pin "2") (pinfunction "2_2") (pintype "passive"))
      (node (ref "U1") (pin "14") (pinfunction "PB2(SS/OC1B)_14") (pintype "bidirectional"))
    )
    (net (code "7") (name "/JU1") (class "Default")
      (node (ref "JP3") (pin "1") (pinfunction "1_1") (pintype "passive"))
      (node (ref "R61") (pin "2") (pinfunction "2_2") (pintype "passive"))
      (node (ref "R64") (pin "1") (pinfunction "1_1") (pintype "passive"))
    )
    (net (code "8") (name "/JU2") (class "Default")
      (node (ref "JP4") (pin "1") (pinfunction "1_1") (pintype "passive"))
      (node (ref "R62") (pin "2") (pinfunction "2_2") (pintype "passive"))
      (node (ref "R65") (pin "1") (pinfunction "1_1") (pintype "passive"))
    )
    (net (code "9") (name "/JU3") (class "Default")
      (node (ref "JP5") (pin "1") (pinfunction "1_1") (pintype "passive"))
      (node (ref "R63") (pin "2") (pinfunction "2_2") (pintype "passive"))
      (node (ref "R66") (pin "1") (pinfunction "1_1") (pintype "passive"))
    )
    (net (code "10") (name "/MISO1") (class "Default")
      (node (ref "J1") (pin "1") (pinfunction "1_1") (pintype "passive"))
      (node (ref "U1") (pin "16") (pinfunction "PB4(MISO)_16") (pintype "bidirectional"))
      (node (ref "U4") (pin "7") (pinfunction "DO_7") (pintype "bidirectional"))
    )
    (net (code "11") (name "/MISO2") (class "Default")
      (node (ref "J2") (pin "1") (pinfunction "1_1") (pintype "passive"))
      (node (ref "R62") (pin "1") (pinfunction "1_1") (pintype "passive"))
      (node (ref "U2") (pin "16") (pinfunction "PB4(MISO)_16") (pintype "bidirectional"))
    )
    (net (code "12") (name "/MOSI1") (class "Default")
      (node (ref "J1") (pin "4") (pinfunction "4_4") (pintype "passive"))
      (node (ref "R55") (pin "1") (pinfunction "1_1") (pintype "passive"))
      (node (ref "U1") (pin "15") (pinfunction "PB3(MOSI/OC2)_15") (pintype "bidirectional"))
    )
    (net (code "13") (name "/MOSI2") (class "Default")
      (node (ref "J2") (pin "4") (pinfunction "4_4") (pintype "passive"))
      (node (ref "R61") (pin "1") (pinfunction "1_1") (pintype "passive"))
      (node (ref "U2") (pin "15") (pinfunction "PB3(MOSI/OC2)_15") (pintype "bidirectional"))
    )
    (net (code "14") (name "/OUT") (class "Default")
      (node (ref "J1") (pin "2") (pinfunction "2_2") (pintype "passive"))
      (node (ref "J2") (pin "2") (pinfunction "2_2") (pintype "passive"))
      (node (ref "R49") (pin "1") (pinfunction "1_1") (pintype "passive"))
      (node (ref "R50") (pin "1") (pinfunction "1_1") (pintype "passive"))
      (node (ref "U1") (pin "18") (pinfunction "AVCC_18") (pintype "bidirectional"))
      (node (ref "U1") (pin "4") (pinfunction "VCC_4") (pintype "bidirectional"))
      (node (ref "U1") (pin "6") (pinfunction "VCC_6") (pintype "bidirectional"))
      (node (ref "U2") (pin "18") (pinfunction "AVCC_18") (pintype "bidirectional"))
      (node (ref "U2") (pin "4") (pinfunction "VCC_4") (pintype "bidirectional"))
      (node (ref "U2") (pin "6") (pinfunction "VCC_6") (pintype "bidirectional"))
      (node (ref "U5") (pin "2") (pinfunction "OUT_2") (pintype "output"))
    )
    (net (code "15") (name "/RST1") (class "Default")
      (node (ref "J1") (pin "5") (pinfunction "5_5") (pintype "passive"))
      (node (ref "R49") (pin "2") (pinfunction "2_2") (pintype "passive"))
      (node (ref "U1") (pin "29") (pinfunction "PC6(/RESET)_29") (pintype "bidirectional"))
    )
    (net (code "16") (name "/RST2") (class "Default")
      (node (ref "J2") (pin "5") (pinfunction "5_5") (pintype "passive"))
      (node (ref "R50") (pin "2") (pinfunction "2_2") (pintype "passive"))
      (node (ref "U2") (pin "29") (pinfunction "PC6(/RESET)_29") (pintype "bidirectional"))
    )
    (net (code "17") (name "/SCK1") (class "Default")
      (node (ref "J1") (pin "3") (pinfunction "3_3") (pintype "passive"))
      (node (ref "R54") (pin "1") (pinfunction "1_1") (pintype "passive"))
      (node (ref "U1") (pin "17") (pinfunction "PB5(SCK)_17") (pintype "bidirectional"))
    )
    (net (code "18") (name "/SCK2") (class "Default")
      (node (ref "J2") (pin "3") (pinfunction "3_3") (pintype "passive"))
      (node (ref "R63") (pin "1") (pinfunction "1_1") (pintype "passive"))
      (node (ref "U2") (pin "17") (pinfunction "PB5(SCK)_17") (pintype "bidirectional"))
    )
    (net (code "19") (name "/SDA") (class "Default")
      (node (ref "U1") (pin "27") (pinfunction "PC4(ADC4/SDA)_27") (pintype "bidirectional"))
      (node (ref "U2") (pin "27") (pinfunction "PC4(ADC4/SDA)_27") (pintype "bidirectional"))
    )
    (net (code "20") (name "/_CS1") (class "Default")
      (node (ref "ADS1") (pin "39") (pinfunction "CS_39") (pintype "input"))
      (node (ref "ARDUINO_CONN") (pin "1") (pinfunction "1_1") (pintype "passive"))
      (node (ref "R22") (pin "1") (pinfunction "1_1") (pintype "passive"))
      (node (ref "U2") (pin "11") (pinfunction "PD7(AIN1)_11") (pintype "bidirectional"))
    )
    (net (code "21") (name "/_CS2") (class "Default")
      (node (ref "ADS2") (pin "39") (pinfunction "CS_39") (pintype "input"))
      (node (ref "ARDUINO_CONN") (pin "2") (pinfunction "2_2") (pintype "passive"))
      (node (ref "R81") (pin "1") (pinfunction "1_1") (pintype "passive"))
      (node (ref "U2") (pin "12") (pinfunction "PB0(ICP)_12") (pintype "bidirectional"))
    )
    (net (code "22") (name "/_CS3") (class "Default")
      (node (ref "ADS3") (pin "39") (pinfunction "CS_39") (pintype "input"))
      (node (ref "ARDUINO_CONN") (pin "3") (pinfunction "3_3") (pintype "passive"))
      (node (ref "R82") (pin "1") (pinfunction "1_1") (pintype "passive"))
      (node (ref "U2") (pin "13") (pinfunction "PB1(OC1A)_13") (pintype "bidirectional"))
    )
    (net (code "23") (name "/_CS4") (class "Default")
      (node (ref "ADS4") (pin "39") (pinfunction "CS_39") (pintype "input"))
      (node (ref "ARDUINO_CONN") (pin "7") (pinfunction "7_7") (pintype "passive"))
      (node (ref "R83") (pin "1") (pinfunction "1_1") (pintype "passive"))
      (node (ref "U2") (pin "14") (pinfunction "PB2(SS/OC1B)_14") (pintype "bidirectional"))
    )
    (net (code "24") (name "/_DIN") (class "Default")
      (node (ref "ADS1") (pin "34") (pinfunction "DIN_34") (pintype "input"))
      (node (ref "ADS2") (pin "34") (pinfunction "DIN_34") (pintype "input"))
      (node (ref "ADS3") (pin "34") (pinfunction "DIN_34") (pintype "input"))
      (node (ref "ADS4") (pin "34") (pinfunction "DIN_34") (pintype "input"))
      (node (ref "ARDUINO_CONN") (pin "11") (pinfunction "11_11") (pintype "passive"))
      (node (ref "JP3") (pin "2") (pinfunction "2_2") (pintype "passive"))
    )
    (net (code "25") (name "/_DOUT") (class "Default")
      (node (ref "ADS1") (pin "43") (pinfunction "DOUT_43") (pintype "output"))
      (node (ref "ADS2") (pin "43") (pinfunction "DOUT_43") (pintype "output"))
      (node (ref "ADS3") (pin "43") (pinfunction "DOUT_43") (pintype "output"))
      (node (ref "ADS4") (pin "43") (pinfunction "DOUT_43") (pintype "output"))
      (node (ref "ARDUINO_CONN") (pin "5") (pinfunction "5_5") (pintype "passive"))
      (node (ref "JP4") (pin "2") (pinfunction "2_2") (pintype "passive"))
    )
    (net (code "26") (name "/_DRDY") (class "Default")
      (node (ref "ADS1") (pin "47") (pinfunction "DRDY_47") (pintype "output"))
      (node (ref "ADS2") (pin "47") (pinfunction "DRDY_47") (pintype "output"))
      (node (ref "ADS3") (pin "47") (pinfunction "DRDY_47") (pintype "output"))
      (node (ref "ADS4") (pin "47") (pinfunction "DRDY_47") (pintype "output"))
      (node (ref "ARDUINO_CONN") (pin "4") (pinfunction "4_4") (pintype "passive"))
      (node (ref "R21") (pin "1") (pinfunction "1_1") (pintype "passive"))
      (node (ref "U2") (pin "10") (pinfunction "PD6(AIN0)_10") (pintype "bidirectional"))
    )
    (net (code "27") (name "/_PD") (class "Default")
      (node (ref "ADS1") (pin "35") (pinfunction "PWDN_35") (pintype "input"))
      (node (ref "ADS2") (pin "35") (pinfunction "PWDN_35") (pintype "input"))
      (node (ref "ADS3") (pin "35") (pinfunction "PWDN_35") (pintype "input"))
      (node (ref "ADS4") (pin "35") (pinfunction "PWDN_35") (pintype "input"))
      (node (ref "ARDUINO_CONN") (pin "10") (pinfunction "10_10") (pintype "passive"))
      (node (ref "U2") (pin "23") (pinfunction "PC0(ADC0)_23") (pintype "bidirectional"))
    )
    (net (code "28") (name "/_RST") (class "Default")
      (node (ref "ADS1") (pin "36") (pinfunction "RESET_36") (pintype "input"))
      (node (ref "ADS2") (pin "36") (pinfunction "RESET_36") (pintype "input"))
      (node (ref "ADS3") (pin "36") (pinfunction "RESET_36") (pintype "input"))
      (node (ref "ADS4") (pin "36") (pinfunction "RESET_36") (pintype "input"))
      (node (ref "ARDUINO_CONN") (pin "9") (pinfunction "9_9") (pintype "passive"))
      (node (ref "R24") (pin "1") (pinfunction "1_1") (pintype "passive"))
      (node (ref "U2") (pin "32") (pinfunction "PD2(INT0)_32") (pintype "bidirectional"))
    )
    (net (code "29") (name "/_SCLK") (class "Default")
      (node (ref "ADS1") (pin "40") (pinfunction "SCLK_40") (pintype "input"))
      (node (ref "ADS2") (pin "40") (pinfunction "SCLK_40") (pintype "input"))
      (node (ref "ADS3") (pin "40") (pinfunction "SCLK_40") (pintype "input"))
      (node (ref "ADS4") (pin "40") (pinfunction "SCLK_40") (pintype "input"))
      (node (ref "ARDUINO_CONN") (pin "6") (pinfunction "6_6") (pintype "passive"))
      (node (ref "JP5") (pin "2") (pinfunction "2_2") (pintype "passive"))
    )
    (net (code "30") (name "/_SRB2") (class "Default")
      (node (ref "ADS1") (pin "18") (pinfunction "SRB2_18") (pintype "bidirectional"))
      (node (ref "ADS2") (pin "18") (pinfunction "SRB2_18") (pintype "bidirectional"))
      (node (ref "ADS3") (pin "18") (pinfunction "SRB2_18") (pintype "bidirectional"))
      (node (ref "ADS4") (pin "18") (pinfunction "SRB2_18") (pintype "bidirectional"))
      (node (ref "C18") (pin "2") (pinfunction "2_2") (pintype "passive"))
      (node (ref "R18") (pin "2") (pinfunction "2_2") (pintype "passive"))
    )
    (net (code "31") (name "/_STRT") (class "Default")
      (node (ref "ADS1") (pin "38") (pinfunction "START_38") (pintype "input"))
      (node (ref "ADS2") (pin "38") (pinfunction "START_38") (pintype "input"))
      (node (ref "ADS3") (pin "38") (pinfunction "START_38") (pintype "input"))
      (node (ref "ADS4") (pin "38") (pinfunction "START_38") (pintype "input"))
      (node (ref "ARDUINO_CONN") (pin "8") (pinfunction "8_8") (pintype "passive"))
      (node (ref "R23") (pin "1") (pinfunction "1_1") (pintype "passive"))
      (node (ref "U2") (pin "9") (pinfunction "PD5(T1)_9") (pintype "bidirectional"))
    )
    (net (code "32") (name "AGND") (class "Default")
      (node (ref "ADS1") (pin "31") (pinfunction "RESV1_31") (pintype "input"))
      (node (ref "ADS1") (pin "33") (pinfunction "DGND3_33") (pintype "power_in"))
      (node (ref "ADS1") (pin "41") (pinfunction "DAISY_IN_41") (pintype "input"))
      (node (ref "ADS1") (pin "42") (pinfunction "GPIO1_42") (pintype "bidirectional"))
      (node (ref "ADS1") (pin "44") (pinfunction "GPIO2_44") (pintype "bidirectional"))
      (node (ref "ADS1") (pin "45") (pinfunction "GPIO3_45") (pintype "bidirectional"))
      (node (ref "ADS1") (pin "46") (pinfunction "GPIO4_46") (pintype "bidirectional"))
      (node (ref "ADS1") (pin "49") (pinfunction "DGND2_49") (pintype "power_in"))
      (node (ref "ADS1") (pin "51") (pinfunction "DGND1_51") (pintype "power_in"))
      (node (ref "ADS2") (pin "31") (pinfunction "RESV1_31") (pintype "input"))
      (node (ref "ADS2") (pin "33") (pinfunction "DGND3_33") (pintype "power_in"))
      (node (ref "ADS2") (pin "41") (pinfunction "DAISY_IN_41") (pintype "input"))
      (node (ref "ADS2") (pin "42") (pinfunction "GPIO1_42") (pintype "bidirectional"))
      (node (ref "ADS2") (pin "44") (pinfunction "GPIO2_44") (pintype "bidirectional"))
      (node (ref "ADS2") (pin "45") (pinfunction "GPIO3_45") (pintype "bidirectional"))
      (node (ref "ADS2") (pin "46") (pinfunction "GPIO4_46") (pintype "bidirectional"))
      (node (ref "ADS2") (pin "49") (pinfunction "DGND2_49") (pintype "power_in"))
      (node (ref "ADS2") (pin "51") (pinfunction "DGND1_51") (pintype "power_in"))
      (node (ref "ADS2") (pin "52") (pinfunction "CLKSEL_52") (pintype "input"))
      (node (ref "ADS3") (pin "31") (pinfunction "RESV1_31") (pintype "input"))
      (node (ref "ADS3") (pin "33") (pinfunction "DGND3_33") (pintype "power_in"))
      (node (ref "ADS3") (pin "41") (pinfunction "DAISY_IN_41") (pintype "input"))
      (node (ref "ADS3") (pin "42") (pinfunction "GPIO1_42") (pintype "bidirectional"))
      (node (ref "ADS3") (pin "44") (pinfunction "GPIO2_44") (pintype "bidirectional"))
      (node (ref "ADS3") (pin "45") (pinfunction "GPIO3_45") (pintype "bidirectional"))
      (node (ref "ADS3") (pin "46") (pinfunction "GPIO4_46") (pintype "bidirectional"))
      (node (ref "ADS3") (pin "49") (pinfunction "DGND2_49") (pintype "power_in"))
      (node (ref "ADS3") (pin "51") (pinfunction "DGND1_51") (pintype "power_in"))
      (node (ref "ADS3") (pin "52") (pinfunction "CLKSEL_52") (pintype "input"))
      (node (ref "ADS4") (pin "31") (pinfunction "RESV1_31") (pintype "input"))
      (node (ref "ADS4") (pin "33") (pinfunction "DGND3_33") (pintype "power_in"))
      (node (ref "ADS4") (pin "41") (pinfunction "DAISY_IN_41") (pintype "input"))
      (node (ref "ADS4") (pin "42") (pinfunction "GPIO1_42") (pintype "bidirectional"))
      (node (ref "ADS4") (pin "44") (pinfunction "GPIO2_44") (pintype "bidirectional"))
      (node (ref "ADS4") (pin "45") (pinfunction "GPIO3_45") (pintype "bidirectional"))
      (node (ref "ADS4") (pin "46") (pinfunction "GPIO4_46") (pintype "bidirectional"))
      (node (ref "ADS4") (pin "49") (pinfunction "DGND2_49") (pintype "power_in"))
      (node (ref "ADS4") (pin "51") (pinfunction "DGND1_51") (pintype "power_in"))
      (node (ref "ADS4") (pin "52") (pinfunction "CLKSEL_52") (pintype "input"))
      (node (ref "BYP1") (pin "1") (pinfunction "1_1") (pintype "passive"))
      (node (ref "C1") (pin "1") (pinfunction "1_1") (pintype "passive"))
      (node (ref "C10") (pin "1") (pinfunction "1_1") (pintype "passive"))
      (node (ref "C11") (pin "1") (pinfunction "1_1") (pintype "passive"))
      (node (ref "C12") (pin "1") (pinfunction "1_1") (pintype "passive"))
      (node (ref "C13") (pin "1") (pinfunction "1_1") (pintype "passive"))
      (node (ref "C14") (pin "1") (pinfunction "1_1") (pintype "passive"))
      (node (ref "C15") (pin "1") (pinfunction "1_1") (pintype "passive"))
      (node (ref "C16") (pin "1") (pinfunction "1_1") (pintype "passive"))
      (node (ref "C17") (pin "1") (pinfunction "1_1") (pintype "passive"))
      (node (ref "C18") (pin "1") (pinfunction "1_1") (pintype "passive"))
      (node (ref "C2") (pin "1") (pinfunction "1_1") (pintype "passive"))
      (node (ref "C20") (pin "1") (pinfunction "1_1") (pintype "passive"))
      (node (ref "C21") (pin "1") (pinfunction "1_1") (pintype "passive"))
      (node (ref "C22") (pin "1") (pinfunction "1_1") (pintype "passive"))
      (node (ref "C23") (pin "1") (pinfunction "1_1") (pintype "passive"))
      (node (ref "C24") (pin "1") (pinfunction "1_1") (pintype "passive"))
      (node (ref "C25") (pin "1") (pinfunction "1_1") (pintype "passive"))
      (node (ref "C26") (pin "1") (pinfunction "1_1") (pintype "passive"))
      (node (ref "C27") (pin "1") (pinfunction "1_1") (pintype "passive"))
      (node (ref "C28") (pin "1") (pinfunction "1_1") (pintype "passive"))
      (node (ref "C29") (pin "1") (pinfunction "1_1") (pintype "passive"))
      (node (ref "C3") (pin "1") (pinfunction "1_1") (pintype "passive"))
      (node (ref "C30") (pin "1") (pinfunction "1_1") (pintype "passive"))
      (node (ref "C31") (pin "1") (pinfunction "1_1") (pintype "passive"))
      (node (ref "C32") (pin "1") (pinfunction "1_1") (pintype "passive"))
      (node (ref "C33") (pin "1") (pinfunction "1_1") (pintype "passive"))
      (node (ref "C34") (pin "1") (pinfunction "1_1") (pintype "passive"))
      (node (ref "C35") (pin "1") (pinfunction "1_1") (pintype "passive"))
      (node (ref "C36") (pin "1") (pinfunction "1_1") (pintype "passive"))
      (node (ref "C37") (pin "1") (pinfunction "1_1") (pintype "passive"))
      (node (ref "C38") (pin "1") (pinfunction "1_1") (pintype "passive"))
      (node (ref "C39") (pin "1") (pinfunction "1_1") (pintype "passive"))
      (node (ref "C4") (pin "1") (pinfunction "1_1") (pintype "passive"))
      (node (ref "C40") (pin "1") (pinfunction "1_1") (pintype "passive"))
      (node (ref "C41") (pin "1") (pinfunction "1_1") (pintype "passive"))
      (node (ref "C42") (pin "1") (pinfunction "1_1") (pintype "passive"))
      (node (ref "C43") (pin "1") (pinfunction "1_1") (pintype "passive"))
      (node (ref "C44") (pin "1") (pinfunction "1_1") (pintype "passive"))
      (node (ref "C45") (pin "1") (pinfunction "1_1") (pintype "passive"))
      (node (ref "C46") (pin "1") (pinfunction "1_1") (pintype "passive"))
      (node (ref "C47") (pin "1") (pinfunction "1_1") (pintype "passive"))
      (node (ref "C48") (pin "1") (pinfunction "1_1") (pintype "passive"))
      (node (ref "C49") (pin "1") (pinfunction "1_1") (pintype "passive"))
      (node (ref "C5") (pin "1") (pinfunction "1_1") (pintype "passive"))
      (node (ref "C6") (pin "1") (pinfunction "1_1") (pintype "passive"))
      (node (ref "C7") (pin "1") (pinfunction "1_1") (pintype "passive"))
      (node (ref "C8") (pin "1") (pinfunction "1_1") (pintype "passive"))
      (node (ref "C9") (pin "1") (pinfunction "1_1") (pintype "passive"))
      (node (ref "DC1") (pin "2") (pinfunction "2_2") (pintype "passive"))
      (node (ref "DC10") (pin "2") (pinfunction "2_2") (pintype "passive"))
      (node (ref "DC11") (pin "2") (pinfunction "2_2") (pintype "passive"))
      (node (ref "DC12") (pin "2") (pinfunction "2_2") (pintype "passive"))
      (node (ref "DC13") (pin "2") (pinfunction "2_2") (pintype "passive"))
      (node (ref "DC14") (pin "2") (pinfunction "2_2") (pintype "passive"))
      (node (ref "DC15") (pin "2") (pinfunction "2_2") (pintype "passive"))
      (node (ref "DC16") (pin "2") (pinfunction "2_2") (pintype "passive"))
      (node (ref "DC17") (pin "2") (pinfunction "2_2") (pintype "passive"))
      (node (ref "DC18") (pin "2") (pinfunction "2_2") (pintype "passive"))
      (node (ref "DC19") (pin "2") (pinfunction "2_2") (pintype "passive"))
      (node (ref "DC2") (pin "2") (pinfunction "2_2") (pintype "passive"))
      (node (ref "DC20") (pin "2") (pinfunction "2_2") (pintype "passive"))
      (node (ref "DC21") (pin "2") (pinfunction "2_2") (pintype "passive"))
      (node (ref "DC22") (pin "2") (pinfunction "2_2") (pintype "passive"))
      (node (ref "DC23") (pin "2") (pinfunction "2_2") (pintype "passive"))
      (node (ref "DC24") (pin "2") (pinfunction "2_2") (pintype "passive"))
      (node (ref "DC25") (pin "2") (pinfunction "2_2") (pintype "passive"))
      (node (ref "DC26") (pin "2") (pinfunction "2_2") (pintype "passive"))
      (node (ref "DC27") (pin "2") (pinfunction "2_2") (pintype "passive"))
      (node (ref "DC28") (pin "2") (pinfunction "2_2") (pintype "passive"))
      (node (ref "DC29") (pin "2") (pinfunction "2_2") (pintype "passive"))
      (node (ref "DC3") (pin "2") (pinfunction "2_2") (pintype "passive"))
      (node (ref "DC30") (pin "2") (pinfunction "2_2") (pintype "passive"))
      (node (ref "DC4") (pin "2") (pinfunction "2_2") (pintype "passive"))
      (node (ref "DC5") (pin "2") (pinfunction "2_2") (pintype "passive"))
      (node (ref "DC6") (pin "2") (pinfunction "2_2") (pintype "passive"))
      (node (ref "DC7") (pin "2") (pinfunction "2_2") (pintype "passive"))
      (node (ref "DC71") (pin "2") (pinfunction "2_2") (pintype "passive"))
      (node (ref "DC72") (pin "2") (pinfunction "2_2") (pintype "passive"))
      (node (ref "DC73") (pin "2") (pinfunction "2_2") (pintype "passive"))
      (node (ref "DC74") (pin "2") (pinfunction "2_2") (pintype "passive"))
      (node (ref "DC75") (pin "2") (pinfunction "2_2") (pintype "passive"))
      (node (ref "DC76") (pin "2") (pinfunction "2_2") (pintype "passive"))
      (node (ref "DC77") (pin "2") (pinfunction "2_2") (pintype "passive"))
      (node (ref "DC78") (pin "2") (pinfunction "2_2") (pintype "passive"))
      (node (ref "DC79") (pin "2") (pinfunction "2_2") (pintype "passive"))
      (node (ref "DC8") (pin "2") (pinfunction "2_2") (pintype "passive"))
      (node (ref "DC80") (pin "2") (pinfunction "2_2") (pintype "passive"))
      (node (ref "DC9") (pin "2") (pinfunction "2_2") (pintype "passive"))
      (node (ref "J1") (pin "6") (pinfunction "6_6") (pintype "passive"))
      (node (ref "J2") (pin "6") (pinfunction "6_6") (pintype "passive"))
      (node (ref "LED1") (pin "C") (pinfunction "C_C") (pintype "passive"))
      (node (ref "LED3") (pin "C") (pinfunction "C_C") (pintype "passive"))
      (node (ref "LED4") (pin "C") (pinfunction "C_C") (pintype "passive"))
      (node (ref "LED5") (pin "C") (pinfunction "C_C") (pintype "passive"))
      (node (ref "LM1117") (pin "1") (pinfunction "GND_1") (pintype "power_in"))
      (node (ref "LM2663") (pin "1") (pinfunction "EN_1") (pintype "input"))
      (node (ref "LM2663") (pin "3") (pinfunction "GND_3") (pintype "power_in"))
      (node (ref "LM2663") (pin "6") (pinfunction "LV_6") (pintype "bidirectional"))
      (node (ref "LP590725") (pin "2") (pinfunction "GND_2") (pintype "power_in"))
      (node (ref "LP590733") (pin "2") (pinfunction "GND_2") (pintype "power_in"))
      (node (ref "PDC1") (pin "2") (pinfunction "2_2") (pintype "passive"))
      (node (ref "PDC2") (pin "2") (pinfunction "2_2") (pintype "passive"))
      (node (ref "PDC3") (pin "1") (pinfunction "1_1") (pintype "passive"))
      (node (ref "PDC4") (pin "1") (pinfunction "1_1") (pintype "passive"))
      (node (ref "PDC5") (pin "2") (pinfunction "2_2") (pintype "passive"))
      (node (ref "PDC6") (pin "1") (pinfunction "1_1") (pintype "passive"))
      (node (ref "PDC7") (pin "2") (pinfunction "2_2") (pintype "passive"))
      (node (ref "PDC8") (pin "2") (pinfunction "2_2") (pintype "passive"))
      (node (ref "POWER_PIN") (pin "2") (pinfunction "2_2") (pintype "passive"))
      (node (ref "POWER_PLUG") (pin "1") (pinfunction "1_1") (pintype "passive"))
      (node (ref "POWER_PLUG") (pin "2") (pinfunction "2_2") (pintype "passive"))
      (node (ref "R51") (pin "1") (pinfunction "1_1") (pintype "passive"))
      (node (ref "R52") (pin "1") (pinfunction "1_1") (pintype "passive"))
      (node (ref "R53") (pin "1") (pinfunction "1_1") (pintype "passive"))
      (node (ref "R64") (pin "2") (pinfunction "2_2") (pintype "passive"))
      (node (ref "R65") (pin "2") (pinfunction "2_2") (pintype "passive"))
      (node (ref "R66") (pin "2") (pinfunction "2_2") (pintype "passive"))
      (node (ref "TPS72325") (pin "1") (pinfunction "GND_1") (pintype "power_in"))
      (node (ref "U1") (pin "21") (pinfunction "AGND_21") (pintype "bidirectional"))
      (node (ref "U1") (pin "3") (pinfunction "GND_3") (pintype "bidirectional"))
      (node (ref "U1") (pin "5") (pinfunction "GND_5") (pintype "bidirectional"))
      (node (ref "U2") (pin "21") (pinfunction "AGND_21") (pintype "bidirectional"))
      (node (ref "U2") (pin "3") (pinfunction "GND_3") (pintype "bidirectional"))
      (node (ref "U2") (pin "5") (pinfunction "GND_5") (pintype "bidirectional"))
      (node (ref "U4") (pin "GND1") (pinfunction "SHIELD_GND1") (pintype "bidirectional"))
      (node (ref "U4") (pin "GND2") (pinfunction "SHIELD_GND2") (pintype "bidirectional"))
      (node (ref "U5") (pin "1") (pinfunction "ADJ_1") (pintype "input"))
    )
    (net (code "33") (name "AVDD") (class "Default")
      (node (ref "ADS1") (pin "19") (pinfunction "AVDD1_19") (pintype "power_in"))
      (node (ref "ADS1") (pin "21") (pinfunction "AVDD2_21") (pintype "power_in"))
      (node (ref "ADS1") (pin "22") (pinfunction "AVDD3_22") (pintype "power_in"))
      (node (ref "ADS1") (pin "54") (pinfunction "AVDD5_54") (pintype "power_in"))
      (node (ref "ADS1") (pin "56") (pinfunction "AVDD4_56") (pintype "power_in"))
      (node (ref "ADS1") (pin "59") (pinfunction "AVDD_CP_59") (pintype "power_in"))
      (node (ref "ADS2") (pin "19") (pinfunction "AVDD1_19") (pintype "power_in"))
      (node (ref "ADS2") (pin "21") (pinfunction "AVDD2_21") (pintype "power_in"))
      (node (ref "ADS2") (pin "22") (pinfunction "AVDD3_22") (pintype "power_in"))
      (node (ref "ADS2") (pin "54") (pinfunction "AVDD5_54") (pintype "power_in"))
      (node (ref "ADS2") (pin "56") (pinfunction "AVDD4_56") (pintype "power_in"))
      (node (ref "ADS2") (pin "59") (pinfunction "AVDD_CP_59") (pintype "power_in"))
      (node (ref "ADS3") (pin "19") (pinfunction "AVDD1_19") (pintype "power_in"))
      (node (ref "ADS3") (pin "21") (pinfunction "AVDD2_21") (pintype "power_in"))
      (node (ref "ADS3") (pin "22") (pinfunction "AVDD3_22") (pintype "power_in"))
      (node (ref "ADS3") (pin "54") (pinfunction "AVDD5_54") (pintype "power_in"))
      (node (ref "ADS3") (pin "56") (pinfunction "AVDD4_56") (pintype "power_in"))
      (node (ref "ADS3") (pin "59") (pinfunction "AVDD_CP_59") (pintype "power_in"))
      (node (ref "ADS4") (pin "19") (pinfunction "AVDD1_19") (pintype "power_in"))
      (node (ref "ADS4") (pin "21") (pinfunction "AVDD2_21") (pintype "power_in"))
      (node (ref "ADS4") (pin "22") (pinfunction "AVDD3_22") (pintype "power_in"))
      (node (ref "ADS4") (pin "54") (pinfunction "AVDD5_54") (pintype "power_in"))
      (node (ref "ADS4") (pin "56") (pinfunction "AVDD4_56") (pintype "power_in"))
      (node (ref "ADS4") (pin "59") (pinfunction "AVDD_CP_59") (pintype "power_in"))
      (node (ref "DC13") (pin "1") (pinfunction "1_1") (pintype "passive"))
      (node (ref "DC14") (pin "1") (pinfunction "1_1") (pintype "passive"))
      (node (ref "DC17") (pin "1") (pinfunction "1_1") (pintype "passive"))
      (node (ref "DC18") (pin "1") (pinfunction "1_1") (pintype "passive"))
      (node (ref "DC23") (pin "1") (pinfunction "1_1") (pintype "passive"))
      (node (ref "DC24") (pin "1") (pinfunction "1_1") (pintype "passive"))
      (node (ref "DC27") (pin "1") (pinfunction "1_1") (pintype "passive"))
      (node (ref "DC28") (pin "1") (pinfunction "1_1") (pintype "passive"))
      (node (ref "DC3") (pin "1") (pinfunction "1_1") (pintype "passive"))
      (node (ref "DC4") (pin "1") (pinfunction "1_1") (pintype "passive"))
      (node (ref "DC5") (pin "1") (pinfunction "1_1") (pintype "passive"))
      (node (ref "DC6") (pin "1") (pinfunction "1_1") (pintype "passive"))
      (node (ref "DC73") (pin "1") (pinfunction "1_1") (pintype "passive"))
      (node (ref "DC74") (pin "1") (pinfunction "1_1") (pintype "passive"))
      (node (ref "DC77") (pin "1") (pinfunction "1_1") (pintype "passive"))
      (node (ref "DC78") (pin "1") (pinfunction "1_1") (pintype "passive"))
      (node (ref "LP590725") (pin "5") (pinfunction "VOUT_5") (pintype "power_in"))
      (node (ref "PDC4") (pin "2") (pinfunction "2_2") (pintype "passive"))
    )
    (net (code "34") (name "AVSS") (class "Default")
      (node (ref "ADS1") (pin "20") (pinfunction "AVSS1_20") (pintype "power_in"))
      (node (ref "ADS1") (pin "23") (pinfunction "AVSS2_23") (pintype "power_in"))
      (node (ref "ADS1") (pin "25") (pinfunction "VREFN_25") (pintype "input"))
      (node (ref "ADS1") (pin "32") (pinfunction "AVSS3_32") (pintype "power_in"))
      (node (ref "ADS1") (pin "53") (pinfunction "AVSS5_53") (pintype "power_in"))
      (node (ref "ADS1") (pin "57") (pinfunction "AVSS4_57") (pintype "power_in"))
      (node (ref "ADS1") (pin "58") (pinfunction "AVSS_CP_58") (pintype "power_in"))
      (node (ref "ADS2") (pin "20") (pinfunction "AVSS1_20") (pintype "power_in"))
      (node (ref "ADS2") (pin "23") (pinfunction "AVSS2_23") (pintype "power_in"))
      (node (ref "ADS2") (pin "25") (pinfunction "VREFN_25") (pintype "input"))
      (node (ref "ADS2") (pin "32") (pinfunction "AVSS3_32") (pintype "power_in"))
      (node (ref "ADS2") (pin "53") (pinfunction "AVSS5_53") (pintype "power_in"))
      (node (ref "ADS2") (pin "57") (pinfunction "AVSS4_57") (pintype "power_in"))
      (node (ref "ADS2") (pin "58") (pinfunction "AVSS_CP_58") (pintype "power_in"))
      (node (ref "ADS3") (pin "20") (pinfunction "AVSS1_20") (pintype "power_in"))
      (node (ref "ADS3") (pin "23") (pinfunction "AVSS2_23") (pintype "power_in"))
      (node (ref "ADS3") (pin "25") (pinfunction "VREFN_25") (pintype "input"))
      (node (ref "ADS3") (pin "32") (pinfunction "AVSS3_32") (pintype "power_in"))
      (node (ref "ADS3") (pin "53") (pinfunction "AVSS5_53") (pintype "power_in"))
      (node (ref "ADS3") (pin "57") (pinfunction "AVSS4_57") (pintype "power_in"))
      (node (ref "ADS3") (pin "58") (pinfunction "AVSS_CP_58") (pintype "power_in"))
      (node (ref "ADS4") (pin "20") (pinfunction "AVSS1_20") (pintype "power_in"))
      (node (ref "ADS4") (pin "23") (pinfunction "AVSS2_23") (pintype "power_in"))
      (node (ref "ADS4") (pin "25") (pinfunction "VREFN_25") (pintype "input"))
      (node (ref "ADS4") (pin "32") (pinfunction "AVSS3_32") (pintype "power_in"))
      (node (ref "ADS4") (pin "53") (pinfunction "AVSS5_53") (pintype "power_in"))
      (node (ref "ADS4") (pin "57") (pinfunction "AVSS4_57") (pintype "power_in"))
      (node (ref "ADS4") (pin "58") (pinfunction "AVSS_CP_58") (pintype "power_in"))
      (node (ref "DC10") (pin "1") (pinfunction "1_1") (pintype "passive"))
      (node (ref "DC11") (pin "1") (pinfunction "1_1") (pintype "passive"))
      (node (ref "DC12") (pin "1") (pinfunction "1_1") (pintype "passive"))
      (node (ref "DC19") (pin "1") (pinfunction "1_1") (pintype "passive"))
      (node (ref "DC20") (pin "1") (pinfunction "1_1") (pintype "passive"))
      (node (ref "DC21") (pin "1") (pinfunction "1_1") (pintype "passive"))
      (node (ref "DC22") (pin "1") (pinfunction "1_1") (pintype "passive"))
      (node (ref "DC29") (pin "1") (pinfunction "1_1") (pintype "passive"))
      (node (ref "DC30") (pin "1") (pinfunction "1_1") (pintype "passive"))
      (node (ref "DC7") (pin "1") (pinfunction "1_1") (pintype "passive"))
      (node (ref "DC71") (pin "1") (pinfunction "1_1") (pintype "passive"))
      (node (ref "DC72") (pin "1") (pinfunction "1_1") (pintype "passive"))
      (node (ref "DC79") (pin "1") (pinfunction "1_1") (pintype "passive"))
      (node (ref "DC8") (pin "1") (pinfunction "1_1") (pintype "passive"))
      (node (ref "DC80") (pin "1") (pinfunction "1_1") (pintype "passive"))
      (node (ref "DC9") (pin "1") (pinfunction "1_1") (pintype "passive"))
      (node (ref "PDC8") (pin "1") (pinfunction "1_1") (pintype "passive"))
      (node (ref "TPS72325") (pin "5") (pinfunction "VOUT_5") (pintype "power_in"))
      (node (ref "VC1.1") (pin "2") (pinfunction "2_2") (pintype "passive"))
      (node (ref "VC1.2") (pin "2") (pinfunction "2_2") (pintype "passive"))
      (node (ref "VC1.3") (pin "2") (pinfunction "2_2") (pintype "passive"))
      (node (ref "VC1.4") (pin "2") (pinfunction "2_2") (pintype "passive"))
      (node (ref "VC2.1") (pin "2") (pinfunction "2_2") (pintype "passive"))
      (node (ref "VC2.2") (pin "2") (pinfunction "2_2") (pintype "passive"))
      (node (ref "VC2.3") (pin "2") (pinfunction "2_2") (pintype "passive"))
      (node (ref "VC2.4") (pin "2") (pinfunction "2_2") (pintype "passive"))
      (node (ref "VC3,1.1") (pin "2") (pinfunction "2_2") (pintype "passive"))
      (node (ref "VC3,1.2") (pin "2") (pinfunction "2_2") (pintype "passive"))
      (node (ref "VC3,1.3") (pin "2") (pinfunction "2_2") (pintype "passive"))
      (node (ref "VC3,2.1") (pin "2") (pinfunction "2_2") (pintype "passive"))
      (node (ref "VC3,2.2") (pin "2") (pinfunction "2_2") (pintype "passive"))
      (node (ref "VC3,2.3") (pin "2") (pinfunction "2_2") (pintype "passive"))
      (node (ref "VC3.1") (pin "2") (pinfunction "2_2") (pintype "passive"))
      (node (ref "VC3.2") (pin "2") (pinfunction "2_2") (pintype "passive"))
      (node (ref "VC4.1") (pin "2") (pinfunction "2_2") (pintype "passive"))
      (node (ref "VC4.2") (pin "2") (pinfunction "2_2") (pintype "passive"))
      (node (ref "VC4.3") (pin "2") (pinfunction "2_2") (pintype "passive"))
      (node (ref "VC4.4") (pin "2") (pinfunction "2_2") (pintype "passive"))
      (node (ref "VR1.1") (pin "2") (pinfunction "2_2") (pintype "passive"))
      (node (ref "VR1.2") (pin "2") (pinfunction "2_2") (pintype "passive"))
      (node (ref "VR1.3") (pin "2") (pinfunction "2_2") (pintype "passive"))
      (node (ref "VR1.4") (pin "2") (pinfunction "2_2") (pintype "passive"))
      (node (ref "VR2.1") (pin "2") (pinfunction "2_2") (pintype "passive"))
      (node (ref "VR2.2") (pin "2") (pinfunction "2_2") (pintype "passive"))
      (node (ref "VR2.3") (pin "2") (pinfunction "2_2") (pintype "passive"))
      (node (ref "VR2.4") (pin "2") (pinfunction "2_2") (pintype "passive"))
    )
    (net (code "35") (name "DVDD") (class "Default")
      (node (ref "ADS1") (pin "48") (pinfunction "DVDD2_48") (pintype "power_in"))
      (node (ref "ADS1") (pin "50") (pinfunction "DVDD1_50") (pintype "power_in"))
      (node (ref "ADS2") (pin "48") (pinfunction "DVDD2_48") (pintype "power_in"))
      (node (ref "ADS2") (pin "50") (pinfunction "DVDD1_50") (pintype "power_in"))
      (node (ref "ADS3") (pin "48") (pinfunction "DVDD2_48") (pintype "power_in"))
      (node (ref "ADS3") (pin "50") (pinfunction "DVDD1_50") (pintype "power_in"))
      (node (ref "ADS4") (pin "48") (pinfunction "DVDD2_48") (pintype "power_in"))
      (node (ref "ADS4") (pin "50") (pinfunction "DVDD1_50") (pintype "power_in"))
      (node (ref "DC1") (pin "1") (pinfunction "1_1") (pintype "passive"))
      (node (ref "DC15") (pin "1") (pinfunction "1_1") (pintype "passive"))
      (node (ref "DC16") (pin "1") (pinfunction "1_1") (pintype "passive"))
      (node (ref "DC2") (pin "1") (pinfunction "1_1") (pintype "passive"))
      (node (ref "DC25") (pin "1") (pinfunction "1_1") (pintype "passive"))
      (node (ref "DC26") (pin "1") (pinfunction "1_1") (pintype "passive"))
      (node (ref "DC75") (pin "1") (pinfunction "1_1") (pintype "passive"))
      (node (ref "DC76") (pin "1") (pinfunction "1_1") (pintype "passive"))
      (node (ref "LP590733") (pin "5") (pinfunction "VOUT_5") (pintype "power_in"))
      (node (ref "PDC6") (pin "2") (pinfunction "2_2") (pintype "passive"))
      (node (ref "R20") (pin "1") (pinfunction "1_1") (pintype "passive"))
      (node (ref "R21") (pin "2") (pinfunction "2_2") (pintype "passive"))
      (node (ref "R22") (pin "2") (pinfunction "2_2") (pintype "passive"))
      (node (ref "R23") (pin "2") (pinfunction "2_2") (pintype "passive"))
      (node (ref "R24") (pin "2") (pinfunction "2_2") (pintype "passive"))
      (node (ref "R81") (pin "2") (pinfunction "2_2") (pintype "passive"))
      (node (ref "R82") (pin "2") (pinfunction "2_2") (pintype "passive"))
      (node (ref "R83") (pin "2") (pinfunction "2_2") (pintype "passive"))
      (node (ref "U4") (pin "4") (pinfunction "VCC_4") (pintype "bidirectional"))
    )
    (net (code "36") (name "Net-(ADS1-BIASIN)") (class "Default")
      (node (ref "ADS1") (pin "62") (pinfunction "BIASIN_62") (pintype "input"))
      (node (ref "ADS1") (pin "63") (pinfunction "BIASOUT_63") (pintype "output"))
      (node (ref "C1") (pin "2") (pinfunction "2_2") (pintype "passive"))
      (node (ref "C19") (pin "1") (pinfunction "1_1") (pintype "passive"))
      (node (ref "R1") (pin "2") (pinfunction "2_2") (pintype "passive"))
      (node (ref "R19") (pin "1") (pinfunction "1_1") (pintype "passive"))
    )
    (net (code "37") (name "Net-(ADS1-CLK)") (class "Default")
      (node (ref "ADS1") (pin "37") (pinfunction "CLK_37") (pintype "bidirectional"))
      (node (ref "ADS2") (pin "37") (pinfunction "CLK_37") (pintype "bidirectional"))
      (node (ref "ADS3") (pin "37") (pinfunction "CLK_37") (pintype "bidirectional"))
      (node (ref "ADS4") (pin "37") (pinfunction "CLK_37") (pintype "bidirectional"))
    )
    (net (code "38") (name "Net-(ADS1-CLKSEL)") (class "Default")
      (node (ref "ADS1") (pin "52") (pinfunction "CLKSEL_52") (pintype "input"))
      (node (ref "R20") (pin "2") (pinfunction "2_2") (pintype "passive"))
    )
    (net (code "39") (name "Net-(ADS1-IN1N)") (class "Default")
      (node (ref "ADS1") (pin "15") (pinfunction "IN1N_15") (pintype "input"))
      (node (ref "C16") (pin "2") (pinfunction "2_2") (pintype "passive"))
      (node (ref "R16") (pin "2") (pinfunction "2_2") (pintype "passive"))
    )
    (net (code "40") (name "Net-(ADS1-IN1P)") (class "Default")
      (node (ref "ADS1") (pin "16") (pinfunction "IN1P_16") (pintype "input"))
      (node (ref "C17") (pin "2") (pinfunction "2_2") (pintype "passive"))
      (node (ref "R17") (pin "2") (pinfunction "2_2") (pintype "passive"))
    )
    (net (code "41") (name "Net-(ADS1-IN2N)") (class "Default")
      (node (ref "ADS1") (pin "13") (pinfunction "IN2N_13") (pintype "input"))
      (node (ref "C14") (pin "2") (pinfunction "2_2") (pintype "passive"))
      (node (ref "R14") (pin "2") (pinfunction "2_2") (pintype "passive"))
    )
    (net (code "42") (name "Net-(ADS1-IN2P)") (class "Default")
      (node (ref "ADS1") (pin "14") (pinfunction "IN2P_14") (pintype "input"))
      (node (ref "C15") (pin "2") (pinfunction "2_2") (pintype "passive"))
      (node (ref "R15") (pin "2") (pinfunction "2_2") (pintype "passive"))
    )
    (net (code "43") (name "Net-(ADS1-IN3N)") (class "Default")
      (node (ref "ADS1") (pin "11") (pinfunction "IN3N_11") (pintype "input"))
      (node (ref "C12") (pin "2") (pinfunction "2_2") (pintype "passive"))
      (node (ref "R12") (pin "2") (pinfunction "2_2") (pintype "passive"))
    )
    (net (code "44") (name "Net-(ADS1-IN3P)") (class "Default")
      (node (ref "ADS1") (pin "12") (pinfunction "IN3P_12") (pintype "input"))
      (node (ref "C13") (pin "2") (pinfunction "2_2") (pintype "passive"))
      (node (ref "R13") (pin "2") (pinfunction "2_2") (pintype "passive"))
    )
    (net (code "45") (name "Net-(ADS1-IN4N)") (class "Default")
      (node (ref "ADS1") (pin "9") (pinfunction "IN4N_9") (pintype "input"))
      (node (ref "C10") (pin "2") (pinfunction "2_2") (pintype "passive"))
      (node (ref "R10") (pin "2") (pinfunction "2_2") (pintype "passive"))
    )
    (net (code "46") (name "Net-(ADS1-IN4P)") (class "Default")
      (node (ref "ADS1") (pin "10") (pinfunction "IN4P_10") (pintype "input"))
      (node (ref "C11") (pin "2") (pinfunction "2_2") (pintype "passive"))
      (node (ref "R11") (pin "2") (pinfunction "2_2") (pintype "passive"))
    )
    (net (code "47") (name "Net-(ADS1-IN5N)") (class "Default")
      (node (ref "ADS1") (pin "7") (pinfunction "IN5N_7") (pintype "input"))
      (node (ref "C8") (pin "2") (pinfunction "2_2") (pintype "passive"))
      (node (ref "R8") (pin "2") (pinfunction "2_2") (pintype "passive"))
    )
    (net (code "48") (name "Net-(ADS1-IN5P)") (class "Default")
      (node (ref "ADS1") (pin "8") (pinfunction "IN5P_8") (pintype "input"))
      (node (ref "C9") (pin "2") (pinfunction "2_2") (pintype "passive"))
      (node (ref "R9") (pin "2") (pinfunction "2_2") (pintype "passive"))
    )
    (net (code "49") (name "Net-(ADS1-IN6N)") (class "Default")
      (node (ref "ADS1") (pin "5") (pinfunction "IN6N_5") (pintype "input"))
      (node (ref "C6") (pin "2") (pinfunction "2_2") (pintype "passive"))
      (node (ref "R6") (pin "2") (pinfunction "2_2") (pintype "passive"))
    )
    (net (code "50") (name "Net-(ADS1-IN6P)") (class "Default")
      (node (ref "ADS1") (pin "6") (pinfunction "IN6P_6") (pintype "input"))
      (node (ref "C7") (pin "2") (pinfunction "2_2") (pintype "passive"))
      (node (ref "R7") (pin "2") (pinfunction "2_2") (pintype "passive"))
    )
    (net (code "51") (name "Net-(ADS1-IN7N)") (class "Default")
      (node (ref "ADS1") (pin "3") (pinfunction "IN7N_3") (pintype "input"))
      (node (ref "C4") (pin "2") (pinfunction "2_2") (pintype "passive"))
      (node (ref "R4") (pin "2") (pinfunction "2_2") (pintype "passive"))
    )
    (net (code "52") (name "Net-(ADS1-IN7P)") (class "Default")
      (node (ref "ADS1") (pin "4") (pinfunction "IN7P_4") (pintype "input"))
      (node (ref "C5") (pin "2") (pinfunction "2_2") (pintype "passive"))
      (node (ref "R5") (pin "2") (pinfunction "2_2") (pintype "passive"))
    )
    (net (code "53") (name "Net-(ADS1-IN8N)") (class "Default")
      (node (ref "ADS1") (pin "1") (pinfunction "IN8N_1") (pintype "input"))
      (node (ref "C2") (pin "2") (pinfunction "2_2") (pintype "passive"))
      (node (ref "R2") (pin "2") (pinfunction "2_2") (pintype "passive"))
    )
    (net (code "54") (name "Net-(ADS1-IN8P)") (class "Default")
      (node (ref "ADS1") (pin "2") (pinfunction "IN8P_2") (pintype "input"))
      (node (ref "C3") (pin "2") (pinfunction "2_2") (pintype "passive"))
      (node (ref "R3") (pin "2") (pinfunction "2_2") (pintype "passive"))
    )
    (net (code "55") (name "Net-(ADS1-VCAP1)") (class "Default")
      (node (ref "ADS1") (pin "28") (pinfunction "VCAP1_28") (pintype "passive"))
      (node (ref "VC1.1") (pin "1") (pinfunction "1_1") (pintype "passive"))
    )
    (net (code "56") (name "Net-(ADS1-VCAP2)") (class "Default")
      (node (ref "ADS1") (pin "30") (pinfunction "VCAP2_30") (pintype "passive"))
      (node (ref "VC2.1") (pin "1") (pinfunction "1_1") (pintype "passive"))
    )
    (net (code "57") (name "Net-(ADS1-VCAP3)") (class "Default")
      (node (ref "ADS1") (pin "55") (pinfunction "VCAP3_55") (pintype "passive"))
      (node (ref "VC3.1") (pin "1") (pinfunction "1_1") (pintype "passive"))
      (node (ref "VC3.2") (pin "1") (pinfunction "1_1") (pintype "passive"))
    )
    (net (code "58") (name "Net-(ADS1-VCAP4)") (class "Default")
      (node (ref "ADS1") (pin "26") (pinfunction "VCAP4_26") (pintype "output"))
      (node (ref "VC4.1") (pin "1") (pinfunction "1_1") (pintype "passive"))
    )
    (net (code "59") (name "Net-(ADS1-VREFP)") (class "Default")
      (node (ref "ADS1") (pin "24") (pinfunction "VREFP_24") (pintype "bidirectional"))
      (node (ref "VR1.1") (pin "1") (pinfunction "1_1") (pintype "passive"))
      (node (ref "VR2.1") (pin "1") (pinfunction "1_1") (pintype "passive"))
    )
    (net (code "60") (name "Net-(ADS2-IN1N)") (class "Default")
      (node (ref "ADS2") (pin "15") (pinfunction "IN1N_15") (pintype "input"))
      (node (ref "C27") (pin "2") (pinfunction "2_2") (pintype "passive"))
      (node (ref "R32") (pin "2") (pinfunction "2_2") (pintype "passive"))
    )
    (net (code "61") (name "Net-(ADS2-IN2N)") (class "Default")
      (node (ref "ADS2") (pin "13") (pinfunction "IN2N_13") (pintype "input"))
      (node (ref "C26") (pin "2") (pinfunction "2_2") (pintype "passive"))
      (node (ref "R31") (pin "2") (pinfunction "2_2") (pintype "passive"))
    )
    (net (code "62") (name "Net-(ADS2-IN3N)") (class "Default")
      (node (ref "ADS2") (pin "11") (pinfunction "IN3N_11") (pintype "input"))
      (node (ref "C25") (pin "2") (pinfunction "2_2") (pintype "passive"))
      (node (ref "R30") (pin "2") (pinfunction "2_2") (pintype "passive"))
    )
    (net (code "63") (name "Net-(ADS2-IN4N)") (class "Default")
      (node (ref "ADS2") (pin "9") (pinfunction "IN4N_9") (pintype "input"))
      (node (ref "C24") (pin "2") (pinfunction "2_2") (pintype "passive"))
      (node (ref "R29") (pin "2") (pinfunction "2_2") (pintype "passive"))
    )
    (net (code "64") (name "Net-(ADS2-IN5N)") (class "Default")
      (node (ref "ADS2") (pin "7") (pinfunction "IN5N_7") (pintype "input"))
      (node (ref "C23") (pin "2") (pinfunction "2_2") (pintype "passive"))
      (node (ref "R28") (pin "2") (pinfunction "2_2") (pintype "passive"))
    )
    (net (code "65") (name "Net-(ADS2-IN6N)") (class "Default")
      (node (ref "ADS2") (pin "5") (pinfunction "IN6N_5") (pintype "input"))
      (node (ref "C22") (pin "2") (pinfunction "2_2") (pintype "passive"))
      (node (ref "R27") (pin "2") (pinfunction "2_2") (pintype "passive"))
    )
    (net (code "66") (name "Net-(ADS2-IN7N)") (class "Default")
      (node (ref "ADS2") (pin "3") (pinfunction "IN7N_3") (pintype "input"))
      (node (ref "C21") (pin "2") (pinfunction "2_2") (pintype "passive"))
      (node (ref "R26") (pin "2") (pinfunction "2_2") (pintype "passive"))
    )
    (net (code "67") (name "Net-(ADS2-IN8N)") (class "Default")
      (node (ref "ADS2") (pin "1") (pinfunction "IN8N_1") (pintype "input"))
      (node (ref "C20") (pin "2") (pinfunction "2_2") (pintype "passive"))
      (node (ref "R25") (pin "2") (pinfunction "2_2") (pintype "passive"))
    )
    (net (code "68") (name "Net-(ADS2-VCAP1)") (class "Default")
      (node (ref "ADS2") (pin "28") (pinfunction "VCAP1_28") (pintype "passive"))
      (node (ref "VC1.2") (pin "1") (pinfunction "1_1") (pintype "passive"))
    )
    (net (code "69") (name "Net-(ADS2-VCAP2)") (class "Default")
      (node (ref "ADS2") (pin "30") (pinfunction "VCAP2_30") (pintype "passive"))
      (node (ref "VC2.2") (pin "1") (pinfunction "1_1") (pintype "passive"))
    )
    (net (code "70") (name "Net-(ADS2-VCAP3)") (class "Default")
      (node (ref "ADS2") (pin "55") (pinfunction "VCAP3_55") (pintype "passive"))
      (node (ref "VC3,1.1") (pin "1") (pinfunction "1_1") (pintype "passive"))
      (node (ref "VC3,2.1") (pin "1") (pinfunction "1_1") (pintype "passive"))
    )
    (net (code "71") (name "Net-(ADS2-VCAP4)") (class "Default")
      (node (ref "ADS2") (pin "26") (pinfunction "VCAP4_26") (pintype "output"))
      (node (ref "VC4.2") (pin "1") (pinfunction "1_1") (pintype "passive"))
    )
    (net (code "72") (name "Net-(ADS2-VREFP)") (class "Default")
      (node (ref "ADS2") (pin "24") (pinfunction "VREFP_24") (pintype "bidirectional"))
      (node (ref "VR1.2") (pin "1") (pinfunction "1_1") (pintype "passive"))
      (node (ref "VR2.2") (pin "1") (pinfunction "1_1") (pintype "passive"))
    )
    (net (code "73") (name "Net-(ADS3-IN1N)") (class "Default")
      (node (ref "ADS3") (pin "15") (pinfunction "IN1N_15") (pintype "input"))
      (node (ref "C35") (pin "2") (pinfunction "2_2") (pintype "passive"))
      (node (ref "R40") (pin "2") (pinfunction "2_2") (pintype "passive"))
    )
    (net (code "74") (name "Net-(ADS3-IN2N)") (class "Default")
      (node (ref "ADS3") (pin "13") (pinfunction "IN2N_13") (pintype "input"))
      (node (ref "C34") (pin "2") (pinfunction "2_2") (pintype "passive"))
      (node (ref "R39") (pin "2") (pinfunction "2_2") (pintype "passive"))
    )
    (net (code "75") (name "Net-(ADS3-IN3N)") (class "Default")
      (node (ref "ADS3") (pin "11") (pinfunction "IN3N_11") (pintype "input"))
      (node (ref "C33") (pin "2") (pinfunction "2_2") (pintype "passive"))
      (node (ref "R38") (pin "2") (pinfunction "2_2") (pintype "passive"))
    )
    (net (code "76") (name "Net-(ADS3-IN4N)") (class "Default")
      (node (ref "ADS3") (pin "9") (pinfunction "IN4N_9") (pintype "input"))
      (node (ref "C32") (pin "2") (pinfunction "2_2") (pintype "passive"))
      (node (ref "R37") (pin "2") (pinfunction "2_2") (pintype "passive"))
    )
    (net (code "77") (name "Net-(ADS3-IN5N)") (class "Default")
      (node (ref "ADS3") (pin "7") (pinfunction "IN5N_7") (pintype "input"))
      (node (ref "C31") (pin "2") (pinfunction "2_2") (pintype "passive"))
      (node (ref "R36") (pin "2") (pinfunction "2_2") (pintype "passive"))
    )
    (net (code "78") (name "Net-(ADS3-IN6N)") (class "Default")
      (node (ref "ADS3") (pin "5") (pinfunction "IN6N_5") (pintype "input"))
      (node (ref "C30") (pin "2") (pinfunction "2_2") (pintype "passive"))
      (node (ref "R35") (pin "2") (pinfunction "2_2") (pintype "passive"))
    )
    (net (code "79") (name "Net-(ADS3-IN7N)") (class "Default")
      (node (ref "ADS3") (pin "3") (pinfunction "IN7N_3") (pintype "input"))
      (node (ref "C29") (pin "2") (pinfunction "2_2") (pintype "passive"))
      (node (ref "R34") (pin "2") (pinfunction "2_2") (pintype "passive"))
    )
    (net (code "80") (name "Net-(ADS3-IN8N)") (class "Default")
      (node (ref "ADS3") (pin "1") (pinfunction "IN8N_1") (pintype "input"))
      (node (ref "C28") (pin "2") (pinfunction "2_2") (pintype "passive"))
      (node (ref "R33") (pin "2") (pinfunction "2_2") (pintype "passive"))
    )
    (net (code "81") (name "Net-(ADS3-VCAP1)") (class "Default")
      (node (ref "ADS3") (pin "28") (pinfunction "VCAP1_28") (pintype "passive"))
      (node (ref "VC1.3") (pin "1") (pinfunction "1_1") (pintype "passive"))
    )
    (net (code "82") (name "Net-(ADS3-VCAP2)") (class "Default")
      (node (ref "ADS3") (pin "30") (pinfunction "VCAP2_30") (pintype "passive"))
      (node (ref "VC2.3") (pin "1") (pinfunction "1_1") (pintype "passive"))
    )
    (net (code "83") (name "Net-(ADS3-VCAP3)") (class "Default")
      (node (ref "ADS3") (pin "55") (pinfunction "VCAP3_55") (pintype "passive"))
      (node (ref "VC3,1.2") (pin "1") (pinfunction "1_1") (pintype "passive"))
      (node (ref "VC3,2.2") (pin "1") (pinfunction "1_1") (pintype "passive"))
    )
    (net (code "84") (name "Net-(ADS3-VCAP4)") (class "Default")
      (node (ref "ADS3") (pin "26") (pinfunction "VCAP4_26") (pintype "output"))
      (node (ref "VC4.3") (pin "1") (pinfunction "1_1") (pintype "passive"))
    )
    (net (code "85") (name "Net-(ADS3-VREFP)") (class "Default")
      (node (ref "ADS3") (pin "24") (pinfunction "VREFP_24") (pintype "bidirectional"))
      (node (ref "VR1.3") (pin "1") (pinfunction "1_1") (pintype "passive"))
      (node (ref "VR2.3") (pin "1") (pinfunction "1_1") (pintype "passive"))
    )
    (net (code "86") (name "Net-(ADS4-IN1N)") (class "Default")
      (node (ref "ADS4") (pin "15") (pinfunction "IN1N_15") (pintype "input"))
      (node (ref "C43") (pin "2") (pinfunction "2_2") (pintype "passive"))
      (node (ref "R48") (pin "2") (pinfunction "2_2") (pintype "passive"))
    )
    (net (code "87") (name "Net-(ADS4-IN2N)") (class "Default")
      (node (ref "ADS4") (pin "13") (pinfunction "IN2N_13") (pintype "input"))
      (node (ref "C42") (pin "2") (pinfunction "2_2") (pintype "passive"))
      (node (ref "R47") (pin "2") (pinfunction "2_2") (pintype "passive"))
    )
    (net (code "88") (name "Net-(ADS4-IN3N)") (class "Default")
      (node (ref "ADS4") (pin "11") (pinfunction "IN3N_11") (pintype "input"))
      (node (ref "C41") (pin "2") (pinfunction "2_2") (pintype "passive"))
      (node (ref "R46") (pin "2") (pinfunction "2_2") (pintype "passive"))
    )
    (net (code "89") (name "Net-(ADS4-IN4N)") (class "Default")
      (node (ref "ADS4") (pin "9") (pinfunction "IN4N_9") (pintype "input"))
      (node (ref "C40") (pin "2") (pinfunction "2_2") (pintype "passive"))
      (node (ref "R45") (pin "2") (pinfunction "2_2") (pintype "passive"))
    )
    (net (code "90") (name "Net-(ADS4-IN5N)") (class "Default")
      (node (ref "ADS4") (pin "7") (pinfunction "IN5N_7") (pintype "input"))
      (node (ref "C39") (pin "2") (pinfunction "2_2") (pintype "passive"))
      (node (ref "R44") (pin "2") (pinfunction "2_2") (pintype "passive"))
    )
    (net (code "91") (name "Net-(ADS4-IN6N)") (class "Default")
      (node (ref "ADS4") (pin "5") (pinfunction "IN6N_5") (pintype "input"))
      (node (ref "C38") (pin "2") (pinfunction "2_2") (pintype "passive"))
      (node (ref "R43") (pin "2") (pinfunction "2_2") (pintype "passive"))
    )
    (net (code "92") (name "Net-(ADS4-IN7N)") (class "Default")
      (node (ref "ADS4") (pin "3") (pinfunction "IN7N_3") (pintype "input"))
      (node (ref "C37") (pin "2") (pinfunction "2_2") (pintype "passive"))
      (node (ref "R42") (pin "2") (pinfunction "2_2") (pintype "passive"))
    )
    (net (code "93") (name "Net-(ADS4-IN8N)") (class "Default")
      (node (ref "ADS4") (pin "1") (pinfunction "IN8N_1") (pintype "input"))
      (node (ref "C36") (pin "2") (pinfunction "2_2") (pintype "passive"))
      (node (ref "R41") (pin "2") (pinfunction "2_2") (pintype "passive"))
    )
    (net (code "94") (name "Net-(ADS4-VCAP1)") (class "Default")
      (node (ref "ADS4") (pin "28") (pinfunction "VCAP1_28") (pintype "passive"))
      (node (ref "VC1.4") (pin "1") (pinfunction "1_1") (pintype "passive"))
    )
    (net (code "95") (name "Net-(ADS4-VCAP2)") (class "Default")
      (node (ref "ADS4") (pin "30") (pinfunction "VCAP2_30") (pintype "passive"))
      (node (ref "VC2.4") (pin "1") (pinfunction "1_1") (pintype "passive"))
    )
    (net (code "96") (name "Net-(ADS4-VCAP3)") (class "Default")
      (node (ref "ADS4") (pin "55") (pinfunction "VCAP3_55") (pintype "passive"))
      (node (ref "VC3,1.3") (pin "1") (pinfunction "1_1") (pintype "passive"))
      (node (ref "VC3,2.3") (pin "1") (pinfunction "1_1") (pintype "passive"))
    )
    (net (code "97") (name "Net-(ADS4-VCAP4)") (class "Default")
      (node (ref "ADS4") (pin "26") (pinfunction "VCAP4_26") (pintype "output"))
      (node (ref "VC4.4") (pin "1") (pinfunction "1_1") (pintype "passive"))
    )
    (net (code "98") (name "Net-(ADS4-VREFP)") (class "Default")
      (node (ref "ADS4") (pin "24") (pinfunction "VREFP_24") (pintype "bidirectional"))
      (node (ref "VR1.4") (pin "1") (pinfunction "1_1") (pintype "passive"))
      (node (ref "VR2.4") (pin "1") (pinfunction "1_1") (pintype "passive"))
    )
    (net (code "99") (name "Net-(ELECTRODES-Pad1)") (class "Default")
      (node (ref "ELECTRODES") (pin "1") (pinfunction "1_1") (pintype "passive"))
      (node (ref "R32") (pin "1") (pinfunction "1_1") (pintype "passive"))
    )
    (net (code "100") (name "Net-(ELECTRODES-Pad2)") (class "Default")
      (node (ref "ELECTRODES") (pin "2") (pinfunction "2_2") (pintype "passive"))
      (node (ref "R31") (pin "1") (pinfunction "1_1") (pintype "passive"))
    )
    (net (code "101") (name "Net-(ELECTRODES-Pad3)") (class "Default")
      (node (ref "ELECTRODES") (pin "3") (pinfunction "3_3") (pintype "passive"))
      (node (ref "R30") (pin "1") (pinfunction "1_1") (pintype "passive"))
    )
    (net (code "102") (name "Net-(ELECTRODES-Pad4)") (class "Default")
      (node (ref "ELECTRODES") (pin "4") (pinfunction "4_4") (pintype "passive"))
      (node (ref "R29") (pin "1") (pinfunction "1_1") (pintype "passive"))
    )
    (net (code "103") (name "Net-(ELECTRODES-Pad5)") (class "Default")
      (node (ref "ELECTRODES") (pin "5") (pinfunction "5_5") (pintype "passive"))
      (node (ref "R28") (pin "1") (pinfunction "1_1") (pintype "passive"))
    )
    (net (code "104") (name "Net-(ELECTRODES-Pad6)") (class "Default")
      (node (ref "ELECTRODES") (pin "6") (pinfunction "6_6") (pintype "passive"))
      (node (ref "R27") (pin "1") (pinfunction "1_1") (pintype "passive"))
    )
    (net (code "105") (name "Net-(ELECTRODES-Pad7)") (class "Default")
      (node (ref "ELECTRODES") (pin "7") (pinfunction "7_7") (pintype "passive"))
      (node (ref "R26") (pin "1") (pinfunction "1_1") (pintype "passive"))
    )
    (net (code "106") (name "Net-(ELECTRODES-Pad8)") (class "Default")
      (node (ref "ELECTRODES") (pin "8") (pinfunction "8_8") (pintype "passive"))
      (node (ref "R25") (pin "1") (pinfunction "1_1") (pintype "passive"))
    )
    (net (code "107") (name "Net-(ELECTRODES1-Pad1)") (class "Default")
      (node (ref "ELECTRODES1") (pin "1") (pinfunction "1_1") (pintype "passive"))
      (node (ref "R40") (pin "1") (pinfunction "1_1") (pintype "passive"))
    )
    (net (code "108") (name "Net-(ELECTRODES1-Pad2)") (class "Default")
      (node (ref "ELECTRODES1") (pin "2") (pinfunction "2_2") (pintype "passive"))
      (node (ref "R39") (pin "1") (pinfunction "1_1") (pintype "passive"))
    )
    (net (code "109") (name "Net-(ELECTRODES1-Pad3)") (class "Default")
      (node (ref "ELECTRODES1") (pin "3") (pinfunction "3_3") (pintype "passive"))
      (node (ref "R38") (pin "1") (pinfunction "1_1") (pintype "passive"))
    )
    (net (code "110") (name "Net-(ELECTRODES1-Pad4)") (class "Default")
      (node (ref "ELECTRODES1") (pin "4") (pinfunction "4_4") (pintype "passive"))
      (node (ref "R37") (pin "1") (pinfunction "1_1") (pintype "passive"))
    )
    (net (code "111") (name "Net-(ELECTRODES1-Pad5)") (class "Default")
      (node (ref "ELECTRODES1") (pin "5") (pinfunction "5_5") (pintype "passive"))
      (node (ref "R36") (pin "1") (pinfunction "1_1") (pintype "passive"))
    )
    (net (code "112") (name "Net-(ELECTRODES1-Pad6)") (class "Default")
      (node (ref "ELECTRODES1") (pin "6") (pinfunction "6_6") (pintype "passive"))
      (node (ref "R35") (pin "1") (pinfunction "1_1") (pintype "passive"))
    )
    (net (code "113") (name "Net-(ELECTRODES1-Pad7)") (class "Default")
      (node (ref "ELECTRODES1") (pin "7") (pinfunction "7_7") (pintype "passive"))
      (node (ref "R34") (pin "1") (pinfunction "1_1") (pintype "passive"))
    )
    (net (code "114") (name "Net-(ELECTRODES1-Pad8)") (class "Default")
      (node (ref "ELECTRODES1") (pin "8") (pinfunction "8_8") (pintype "passive"))
      (node (ref "R33") (pin "1") (pinfunction "1_1") (pintype "passive"))
    )
    (net (code "115") (name "Net-(ELECTRODES2-Pad1)") (class "Default")
      (node (ref "ELECTRODES2") (pin "1") (pinfunction "1_1") (pintype "passive"))
      (node (ref "R48") (pin "1") (pinfunction "1_1") (pintype "passive"))
    )
    (net (code "116") (name "Net-(ELECTRODES2-Pad2)") (class "Default")
      (node (ref "ELECTRODES2") (pin "2") (pinfunction "2_2") (pintype "passive"))
      (node (ref "R47") (pin "1") (pinfunction "1_1") (pintype "passive"))
    )
    (net (code "117") (name "Net-(ELECTRODES2-Pad3)") (class "Default")
      (node (ref "ELECTRODES2") (pin "3") (pinfunction "3_3") (pintype "passive"))
      (node (ref "R46") (pin "1") (pinfunction "1_1") (pintype "passive"))
    )
    (net (code "118") (name "Net-(ELECTRODES2-Pad4)") (class "Default")
      (node (ref "ELECTRODES2") (pin "4") (pinfunction "4_4") (pintype "passive"))
      (node (ref "R45") (pin "1") (pinfunction "1_1") (pintype "passive"))
    )
    (net (code "119") (name "Net-(ELECTRODES2-Pad5)") (class "Default")
      (node (ref "ELECTRODES2") (pin "5") (pinfunction "5_5") (pintype "passive"))
      (node (ref "R44") (pin "1") (pinfunction "1_1") (pintype "passive"))
    )
    (net (code "120") (name "Net-(ELECTRODES2-Pad6)") (class "Default")
      (node (ref "ELECTRODES2") (pin "6") (pinfunction "6_6") (pintype "passive"))
      (node (ref "R43") (pin "1") (pinfunction "1_1") (pintype "passive"))
    )
    (net (code "121") (name "Net-(ELECTRODES2-Pad7)") (class "Default")
      (node (ref "ELECTRODES2") (pin "7") (pinfunction "7_7") (pintype "passive"))
      (node (ref "R42") (pin "1") (pinfunction "1_1") (pintype "passive"))
    )
    (net (code "122") (name "Net-(ELECTRODES2-Pad8)") (class "Default")
      (node (ref "ELECTRODES2") (pin "8") (pinfunction "8_8") (pintype "passive"))
      (node (ref "R41") (pin "1") (pinfunction "1_1") (pintype "passive"))
    )
    (net (code "123") (name "Net-(ELECTRODES_P&N-Pad1)") (class "Default")
      (node (ref "ELECTRODES_P&N") (pin "1") (pinfunction "1_1") (pintype "passive"))
      (node (ref "R18") (pin "1") (pinfunction "1_1") (pintype "passive"))
    )
    (net (code "124") (name "Net-(ELECTRODES_P&N-Pad2)") (class "Default")
      (node (ref "ELECTRODES_P&N") (pin "2") (pinfunction "2_2") (pintype "passive"))
      (node (ref "R17") (pin "1") (pinfunction "1_1") (pintype "passive"))
    )
    (net (code "125") (name "Net-(ELECTRODES_P&N-Pad3)") (class "Default")
      (node (ref "ELECTRODES_P&N") (pin "3") (pinfunction "3_3") (pintype "passive"))
      (node (ref "R16") (pin "1") (pinfunction "1_1") (pintype "passive"))
    )
    (net (code "126") (name "Net-(ELECTRODES_P&N-Pad4)") (class "Default")
      (node (ref "ELECTRODES_P&N") (pin "4") (pinfunction "4_4") (pintype "passive"))
      (node (ref "R15") (pin "1") (pinfunction "1_1") (pintype "passive"))
    )
    (net (code "127") (name "Net-(ELECTRODES_P&N-Pad5)") (class "Default")
      (node (ref "ELECTRODES_P&N") (pin "5") (pinfunction "5_5") (pintype "passive"))
      (node (ref "R14") (pin "1") (pinfunction "1_1") (pintype "passive"))
    )
    (net (code "128") (name "Net-(ELECTRODES_P&N-Pad6)") (class "Default")
      (node (ref "ELECTRODES_P&N") (pin "6") (pinfunction "6_6") (pintype "passive"))
      (node (ref "R13") (pin "1") (pinfunction "1_1") (pintype "passive"))
    )
    (net (code "129") (name "Net-(ELECTRODES_P&N-Pad7)") (class "Default")
      (node (ref "ELECTRODES_P&N") (pin "7") (pinfunction "7_7") (pintype "passive"))
      (node (ref "R12") (pin "1") (pinfunction "1_1") (pintype "passive"))
    )
    (net (code "130") (name "Net-(ELECTRODES_P&N-Pad8)") (class "Default")
      (node (ref "ELECTRODES_P&N") (pin "8") (pinfunction "8_8") (pintype "passive"))
      (node (ref "R11") (pin "1") (pinfunction "1_1") (pintype "passive"))
    )
    (net (code "131") (name "Net-(ELECTRODES_P&N-Pad9)") (class "Default")
      (node (ref "ELECTRODES_P&N") (pin "9") (pinfunction "9_9") (pintype "passive"))
      (node (ref "R10") (pin "1") (pinfunction "1_1") (pintype "passive"))
    )
    (net (code "132") (name "Net-(ELECTRODES_P&N-Pad10)") (class "Default")
      (node (ref "ELECTRODES_P&N") (pin "10") (pinfunction "10_10") (pintype "passive"))
      (node (ref "R9") (pin "1") (pinfunction "1_1") (pintype "passive"))
    )
    (net (code "133") (name "Net-(ELECTRODES_P&N-Pad11)") (class "Default")
      (node (ref "ELECTRODES_P&N") (pin "11") (pinfunction "11_11") (pintype "passive"))
      (node (ref "R8") (pin "1") (pinfunction "1_1") (pintype "passive"))
    )
    (net (code "134") (name "Net-(ELECTRODES_P&N-Pad12)") (class "Default")
      (node (ref "ELECTRODES_P&N") (pin "12") (pinfunction "12_12") (pintype "passive"))
      (node (ref "R7") (pin "1") (pinfunction "1_1") (pintype "passive"))
    )
    (net (code "135") (name "Net-(ELECTRODES_P&N-Pad13)") (class "Default")
      (node (ref "ELECTRODES_P&N") (pin "13") (pinfunction "13_13") (pintype "passive"))
      (node (ref "R6") (pin "1") (pinfunction "1_1") (pintype "passive"))
    )
    (net (code "136") (name "Net-(ELECTRODES_P&N-Pad14)") (class "Default")
      (node (ref "ELECTRODES_P&N") (pin "14") (pinfunction "14_14") (pintype "passive"))
      (node (ref "R5") (pin "1") (pinfunction "1_1") (pintype "passive"))
    )
    (net (code "137") (name "Net-(ELECTRODES_P&N-Pad15)") (class "Default")
      (node (ref "ELECTRODES_P&N") (pin "15") (pinfunction "15_15") (pintype "passive"))
      (node (ref "R4") (pin "1") (pinfunction "1_1") (pintype "passive"))
    )
    (net (code "138") (name "Net-(ELECTRODES_P&N-Pad16)") (class "Default")
      (node (ref "ELECTRODES_P&N") (pin "16") (pinfunction "16_16") (pintype "passive"))
      (node (ref "R3") (pin "1") (pinfunction "1_1") (pintype "passive"))
    )
    (net (code "139") (name "Net-(ELECTRODES_P&N-Pad17)") (class "Default")
      (node (ref "ELECTRODES_P&N") (pin "17") (pinfunction "17_17") (pintype "passive"))
      (node (ref "R2") (pin "1") (pinfunction "1_1") (pintype "passive"))
    )
    (net (code "140") (name "Net-(ELECTRODES_P&N-Pad18)") (class "Default")
      (node (ref "ELECTRODES_P&N") (pin "18") (pinfunction "18_18") (pintype "passive"))
      (node (ref "R1") (pin "1") (pinfunction "1_1") (pintype "passive"))
    )
    (net (code "141") (name "Net-(LED1-PadA)") (class "Default")
      (node (ref "LED1") (pin "A") (pinfunction "A_A") (pintype "passive"))
      (node (ref "R59") (pin "2") (pinfunction "2_2") (pintype "passive"))
    )
    (net (code "142") (name "Net-(LED3-PadA)") (class "Default")
      (node (ref "LED3") (pin "A") (pinfunction "A_A") (pintype "passive"))
      (node (ref "R60") (pin "2") (pinfunction "2_2") (pintype "passive"))
    )
    (net (code "143") (name "Net-(LED4-PadA)") (class "Default")
      (node (ref "LED4") (pin "A") (pinfunction "A_A") (pintype "passive"))
      (node (ref "R57") (pin "2") (pinfunction "2_2") (pintype "passive"))
    )
    (net (code "144") (name "Net-(LED5-PadA)") (class "Default")
      (node (ref "LED5") (pin "A") (pinfunction "A_A") (pintype "passive"))
      (node (ref "R58") (pin "2") (pinfunction "2_2") (pintype "passive"))
    )
    (net (code "145") (name "Net-(LM2663-CAP+)") (class "Default")
      (node (ref "BYP2") (pin "1") (pinfunction "1_1") (pintype "passive"))
      (node (ref "LM2663") (pin "2") (pinfunction "CAP+_2") (pintype "bidirectional"))
    )
    (net (code "146") (name "Net-(LM2663-CAP-)") (class "Default")
      (node (ref "BYP2") (pin "2") (pinfunction "2_2") (pintype "passive"))
      (node (ref "LM2663") (pin "4") (pinfunction "CAP-_4") (pintype "bidirectional"))
    )
    (net (code "147") (name "Net-(TPS72325-BYPASS)") (class "Default")
      (node (ref "BYP1") (pin "2") (pinfunction "2_2") (pintype "passive"))
      (node (ref "TPS72325") (pin "4") (pinfunction "BYPASS_4") (pintype "passive"))
    )
    (net (code "148") (name "Net-(U1-AREF)") (class "Default")
      (node (ref "C49") (pin "2") (pinfunction "2_2") (pintype "passive"))
      (node (ref "U1") (pin "20") (pinfunction "AREF_20") (pintype "bidirectional"))
    )
    (net (code "149") (name "Net-(U1-PB6(XTAL1{slash}TOSC1))") (class "Default")
      (node (ref "C44") (pin "2") (pinfunction "2_2") (pintype "passive"))
      (node (ref "U1") (pin "7") (pinfunction "PB6(XTAL1/TOSC1)_7") (pintype "bidirectional"))
      (node (ref "Y2") (pin "3") (pinfunction "2_3") (pintype "passive"))
    )
    (net (code "150") (name "Net-(U1-PB7(XTAL2{slash}TOSC2))") (class "Default")
      (node (ref "C45") (pin "2") (pinfunction "2_2") (pintype "passive"))
      (node (ref "U1") (pin "8") (pinfunction "PB7(XTAL2/TOSC2)_8") (pintype "bidirectional"))
      (node (ref "Y2") (pin "1") (pinfunction "1_1") (pintype "passive"))
    )
    (net (code "151") (name "Net-(U1-PD0(RXD))") (class "Default")
      (node (ref "JP1") (pin "1") (pinfunction "1_1") (pintype "passive"))
      (node (ref "U1") (pin "30") (pinfunction "PD0(RXD)_30") (pintype "bidirectional"))
    )
    (net (code "152") (name "Net-(U1-PD1(TXD))") (class "Default")
      (node (ref "JP1") (pin "2") (pinfunction "2_2") (pintype "passive"))
      (node (ref "U1") (pin "31") (pinfunction "PD1(TXD)_31") (pintype "bidirectional"))
    )
    (net (code "153") (name "Net-(U1-PD3(INT1))") (class "Default")
      (node (ref "R57") (pin "1") (pinfunction "1_1") (pintype "passive"))
      (node (ref "U1") (pin "1") (pinfunction "PD3(INT1)_1") (pintype "bidirectional"))
    )
    (net (code "154") (name "Net-(U1-PD4(XCK{slash}T0))") (class "Default")
      (node (ref "R58") (pin "1") (pinfunction "1_1") (pintype "passive"))
      (node (ref "U1") (pin "2") (pinfunction "PD4(XCK/T0)_2") (pintype "bidirectional"))
    )
    (net (code "155") (name "Net-(U2-AREF)") (class "Default")
      (node (ref "C48") (pin "2") (pinfunction "2_2") (pintype "passive"))
      (node (ref "U2") (pin "20") (pinfunction "AREF_20") (pintype "bidirectional"))
    )
    (net (code "156") (name "Net-(U2-PB6(XTAL1{slash}TOSC1))") (class "Default")
      (node (ref "C46") (pin "2") (pinfunction "2_2") (pintype "passive"))
      (node (ref "U2") (pin "7") (pinfunction "PB6(XTAL1/TOSC1)_7") (pintype "bidirectional"))
      (node (ref "Y1") (pin "3") (pinfunction "2_3") (pintype "passive"))
    )
    (net (code "157") (name "Net-(U2-PB7(XTAL2{slash}TOSC2))") (class "Default")
      (node (ref "C47") (pin "2") (pinfunction "2_2") (pintype "passive"))
      (node (ref "U2") (pin "8") (pinfunction "PB7(XTAL2/TOSC2)_8") (pintype "bidirectional"))
      (node (ref "Y1") (pin "1") (pinfunction "1_1") (pintype "passive"))
    )
    (net (code "158") (name "Net-(U2-PD0(RXD))") (class "Default")
      (node (ref "JP2") (pin "1") (pinfunction "1_1") (pintype "passive"))
      (node (ref "U2") (pin "30") (pinfunction "PD0(RXD)_30") (pintype "bidirectional"))
    )
    (net (code "159") (name "Net-(U2-PD1(TXD))") (class "Default")
      (node (ref "JP2") (pin "2") (pinfunction "2_2") (pintype "passive"))
      (node (ref "U2") (pin "31") (pinfunction "PD1(TXD)_31") (pintype "bidirectional"))
    )
    (net (code "160") (name "Net-(U2-PD3(INT1))") (class "Default")
      (node (ref "R59") (pin "1") (pinfunction "1_1") (pintype "passive"))
      (node (ref "U2") (pin "1") (pinfunction "PD3(INT1)_1") (pintype "bidirectional"))
    )
    (net (code "161") (name "Net-(U2-PD4(XCK{slash}T0))") (class "Default")
      (node (ref "R60") (pin "1") (pinfunction "1_1") (pintype "passive"))
      (node (ref "U2") (pin "2") (pinfunction "PD4(XCK/T0)_2") (pintype "bidirectional"))
    )
    (net (code "162") (name "Net-(U4-CS)") (class "Default")
      (node (ref "R53") (pin "2") (pinfunction "2_2") (pintype "passive"))
      (node (ref "R56") (pin "1") (pinfunction "1_1") (pintype "passive"))
      (node (ref "U4") (pin "2") (pinfunction "CS_2") (pintype "bidirectional"))
    )
    (net (code "163") (name "Net-(U4-DI)") (class "Default")
      (node (ref "R51") (pin "2") (pinfunction "2_2") (pintype "passive"))
      (node (ref "R55") (pin "2") (pinfunction "2_2") (pintype "passive"))
      (node (ref "U4") (pin "3") (pinfunction "DI_3") (pintype "bidirectional"))
    )
    (net (code "164") (name "Net-(U4-SCK)") (class "Default")
      (node (ref "R52") (pin "2") (pinfunction "2_2") (pintype "passive"))
      (node (ref "R54") (pin "2") (pinfunction "2_2") (pintype "passive"))
      (node (ref "U4") (pin "5") (pinfunction "SCK_5") (pintype "bidirectional"))
    )
    (net (code "165") (name "unconnected-(ADS1-BIASREF-Pad60)") (class "Default")
      (node (ref "ADS1") (pin "60") (pinfunction "BIASREF_60") (pintype "input"))
    )
    (net (code "166") (name "unconnected-(ADS1-NC1-Pad27)") (class "Default")
      (node (ref "ADS1") (pin "27") (pinfunction "NC1_27") (pintype "no_connect"))
    )
    (net (code "167") (name "unconnected-(ADS1-NC2-Pad29)") (class "Default")
      (node (ref "ADS1") (pin "29") (pinfunction "NC2_29") (pintype "no_connect"))
    )
    (net (code "168") (name "unconnected-(ADS1-RESV2-Pad64)") (class "Default")
      (node (ref "ADS1") (pin "64") (pinfunction "RESV2_64") (pintype "no_connect"))
    )
    (net (code "169") (name "unconnected-(ADS1-SRB1-Pad17)") (class "Default")
      (node (ref "ADS1") (pin "17") (pinfunction "SRB1_17") (pintype "bidirectional"))
    )
    (net (code "170") (name "unconnected-(ADS2-BIASIN-Pad62)") (class "Default")
      (node (ref "ADS2") (pin "62") (pinfunction "BIASIN_62") (pintype "input"))
    )
    (net (code "171") (name "unconnected-(ADS2-BIASOUT-Pad63)") (class "Default")
      (node (ref "ADS2") (pin "63") (pinfunction "BIASOUT_63") (pintype "output"))
    )
    (net (code "172") (name "unconnected-(ADS2-BIASREF-Pad60)") (class "Default")
      (node (ref "ADS2") (pin "60") (pinfunction "BIASREF_60") (pintype "input"))
    )
    (net (code "173") (name "unconnected-(ADS2-IN1P-Pad16)") (class "Default")
      (node (ref "ADS2") (pin "16") (pinfunction "IN1P_16") (pintype "input"))
    )
    (net (code "174") (name "unconnected-(ADS2-IN2P-Pad14)") (class "Default")
      (node (ref "ADS2") (pin "14") (pinfunction "IN2P_14") (pintype "input"))
    )
    (net (code "175") (name "unconnected-(ADS2-IN3P-Pad12)") (class "Default")
      (node (ref "ADS2") (pin "12") (pinfunction "IN3P_12") (pintype "input"))
    )
    (net (code "176") (name "unconnected-(ADS2-IN4P-Pad10)") (class "Default")
      (node (ref "ADS2") (pin "10") (pinfunction "IN4P_10") (pintype "input"))
    )
    (net (code "177") (name "unconnected-(ADS2-IN5P-Pad8)") (class "Default")
      (node (ref "ADS2") (pin "8") (pinfunction "IN5P_8") (pintype "input"))
    )
    (net (code "178") (name "unconnected-(ADS2-IN6P-Pad6)") (class "Default")
      (node (ref "ADS2") (pin "6") (pinfunction "IN6P_6") (pintype "input"))
    )
    (net (code "179") (name "unconnected-(ADS2-IN7P-Pad4)") (class "Default")
      (node (ref "ADS2") (pin "4") (pinfunction "IN7P_4") (pintype "input"))
    )
    (net (code "180") (name "unconnected-(ADS2-IN8P-Pad2)") (class "Default")
      (node (ref "ADS2") (pin "2") (pinfunction "IN8P_2") (pintype "input"))
    )
    (net (code "181") (name "unconnected-(ADS2-NC1-Pad27)") (class "Default")
      (node (ref "ADS2") (pin "27") (pinfunction "NC1_27") (pintype "no_connect"))
    )
    (net (code "182") (name "unconnected-(ADS2-NC2-Pad29)") (class "Default")
      (node (ref "ADS2") (pin "29") (pinfunction "NC2_29") (pintype "no_connect"))
    )
    (net (code "183") (name "unconnected-(ADS2-RESV2-Pad64)") (class "Default")
      (node (ref "ADS2") (pin "64") (pinfunction "RESV2_64") (pintype "no_connect"))
    )
    (net (code "184") (name "unconnected-(ADS2-SRB1-Pad17)") (class "Default")
      (node (ref "ADS2") (pin "17") (pinfunction "SRB1_17") (pintype "bidirectional"))
    )
    (net (code "185") (name "unconnected-(ADS3-BIASIN-Pad62)") (class "Default")
      (node (ref "ADS3") (pin "62") (pinfunction "BIASIN_62") (pintype "input"))
    )
    (net (code "186") (name "unconnected-(ADS3-BIASOUT-Pad63)") (class "Default")
      (node (ref "ADS3") (pin "63") (pinfunction "BIASOUT_63") (pintype "output"))
    )
    (net (code "187") (name "unconnected-(ADS3-BIASREF-Pad60)") (class "Default")
      (node (ref "ADS3") (pin "60") (pinfunction "BIASREF_60") (pintype "input"))
    )
    (net (code "188") (name "unconnected-(ADS3-IN1P-Pad16)") (class "Default")
      (node (ref "ADS3") (pin "16") (pinfunction "IN1P_16") (pintype "input"))
    )
    (net (code "189") (name "unconnected-(ADS3-IN2P-Pad14)") (class "Default")
      (node (ref "ADS3") (pin "14") (pinfunction "IN2P_14") (pintype "input"))
    )
    (net (code "190") (name "unconnected-(ADS3-IN3P-Pad12)") (class "Default")
      (node (ref "ADS3") (pin "12") (pinfunction "IN3P_12") (pintype "input"))
    )
    (net (code "191") (name "unconnected-(ADS3-IN4P-Pad10)") (class "Default")
      (node (ref "ADS3") (pin "10") (pinfunction "IN4P_10") (pintype "input"))
    )
    (net (code "192") (name "unconnected-(ADS3-IN5P-Pad8)") (class "Default")
      (node (ref "ADS3") (pin "8") (pinfunction "IN5P_8") (pintype "input"))
    )
    (net (code "193") (name "unconnected-(ADS3-IN6P-Pad6)") (class "Default")
      (node (ref "ADS3") (pin "6") (pinfunction "IN6P_6") (pintype "input"))
    )
    (net (code "194") (name "unconnected-(ADS3-IN7P-Pad4)") (class "Default")
      (node (ref "ADS3") (pin "4") (pinfunction "IN7P_4") (pintype "input"))
    )
    (net (code "195") (name "unconnected-(ADS3-IN8P-Pad2)") (class "Default")
      (node (ref "ADS3") (pin "2") (pinfunction "IN8P_2") (pintype "input"))
    )
    (net (code "196") (name "unconnected-(ADS3-NC1-Pad27)") (class "Default")
      (node (ref "ADS3") (pin "27") (pinfunction "NC1_27") (pintype "no_connect"))
    )
    (net (code "197") (name "unconnected-(ADS3-NC2-Pad29)") (class "Default")
      (node (ref "ADS3") (pin "29") (pinfunction "NC2_29") (pintype "no_connect"))
    )
    (net (code "198") (name "unconnected-(ADS3-RESV2-Pad64)") (class "Default")
      (node (ref "ADS3") (pin "64") (pinfunction "RESV2_64") (pintype "no_connect"))
    )
    (net (code "199") (name "unconnected-(ADS3-SRB1-Pad17)") (class "Default")
      (node (ref "ADS3") (pin "17") (pinfunction "SRB1_17") (pintype "bidirectional"))
    )
    (net (code "200") (name "unconnected-(ADS4-BIASIN-Pad62)") (class "Default")
      (node (ref "ADS4") (pin "62") (pinfunction "BIASIN_62") (pintype "input"))
    )
    (net (code "201") (name "unconnected-(ADS4-BIASOUT-Pad63)") (class "Default")
      (node (ref "ADS4") (pin "63") (pinfunction "BIASOUT_63") (pintype "output"))
    )
    (net (code "202") (name "unconnected-(ADS4-BIASREF-Pad60)") (class "Default")
      (node (ref "ADS4") (pin "60") (pinfunction "BIASREF_60") (pintype "input"))
    )
    (net (code "203") (name "unconnected-(ADS4-IN1P-Pad16)") (class "Default")
      (node (ref "ADS4") (pin "16") (pinfunction "IN1P_16") (pintype "input"))
    )
    (net (code "204") (name "unconnected-(ADS4-IN2P-Pad14)") (class "Default")
      (node (ref "ADS4") (pin "14") (pinfunction "IN2P_14") (pintype "input"))
    )
    (net (code "205") (name "unconnected-(ADS4-IN3P-Pad12)") (class "Default")
      (node (ref "ADS4") (pin "12") (pinfunction "IN3P_12") (pintype "input"))
    )
    (net (code "206") (name "unconnected-(ADS4-IN4P-Pad10)") (class "Default")
      (node (ref "ADS4") (pin "10") (pinfunction "IN4P_10") (pintype "input"))
    )
    (net (code "207") (name "unconnected-(ADS4-IN5P-Pad8)") (class "Default")
      (node (ref "ADS4") (pin "8") (pinfunction "IN5P_8") (pintype "input"))
    )
    (net (code "208") (name "unconnected-(ADS4-IN6P-Pad6)") (class "Default")
      (node (ref "ADS4") (pin "6") (pinfunction "IN6P_6") (pintype "input"))
    )
    (net (code "209") (name "unconnected-(ADS4-IN7P-Pad4)") (class "Default")
      (node (ref "ADS4") (pin "4") (pinfunction "IN7P_4") (pintype "input"))
    )
    (net (code "210") (name "unconnected-(ADS4-IN8P-Pad2)") (class "Default")
      (node (ref "ADS4") (pin "2") (pinfunction "IN8P_2") (pintype "input"))
    )
    (net (code "211") (name "unconnected-(ADS4-NC1-Pad27)") (class "Default")
      (node (ref "ADS4") (pin "27") (pinfunction "NC1_27") (pintype "no_connect"))
    )
    (net (code "212") (name "unconnected-(ADS4-NC2-Pad29)") (class "Default")
      (node (ref "ADS4") (pin "29") (pinfunction "NC2_29") (pintype "no_connect"))
    )
    (net (code "213") (name "unconnected-(ADS4-RESV2-Pad64)") (class "Default")
      (node (ref "ADS4") (pin "64") (pinfunction "RESV2_64") (pintype "no_connect"))
    )
    (net (code "214") (name "unconnected-(ADS4-SRB1-Pad17)") (class "Default")
      (node (ref "ADS4") (pin "17") (pinfunction "SRB1_17") (pintype "bidirectional"))
    )
    (net (code "215") (name "unconnected-(LM2663-OSC-Pad7)") (class "Default")
      (node (ref "LM2663") (pin "7") (pinfunction "OSC_7") (pintype "bidirectional"))
    )
    (net (code "216") (name "unconnected-(LP590725-NC-Pad4)") (class "Default")
      (node (ref "LP590725") (pin "4") (pinfunction "NC_4") (pintype "no_connect"))
    )
    (net (code "217") (name "unconnected-(LP590733-NC-Pad4)") (class "Default")
      (node (ref "LP590733") (pin "4") (pinfunction "NC_4") (pintype "no_connect"))
    )
    (net (code "218") (name "unconnected-(U1-ADC6-Pad19)") (class "Default")
      (node (ref "U1") (pin "19") (pinfunction "ADC6_19") (pintype "bidirectional"))
    )
    (net (code "219") (name "unconnected-(U1-ADC7-Pad22)") (class "Default")
      (node (ref "U1") (pin "22") (pinfunction "ADC7_22") (pintype "bidirectional"))
    )
    (net (code "220") (name "unconnected-(U1-PB0(ICP)-Pad12)") (class "Default")
      (node (ref "U1") (pin "12") (pinfunction "PB0(ICP)_12") (pintype "bidirectional"))
    )
    (net (code "221") (name "unconnected-(U1-PB1(OC1A)-Pad13)") (class "Default")
      (node (ref "U1") (pin "13") (pinfunction "PB1(OC1A)_13") (pintype "bidirectional"))
    )
    (net (code "222") (name "unconnected-(U1-PC0(ADC0)-Pad23)") (class "Default")
      (node (ref "U1") (pin "23") (pinfunction "PC0(ADC0)_23") (pintype "bidirectional"))
    )
    (net (code "223") (name "unconnected-(U1-PC1(ADC1)-Pad24)") (class "Default")
      (node (ref "U1") (pin "24") (pinfunction "PC1(ADC1)_24") (pintype "bidirectional"))
    )
    (net (code "224") (name "unconnected-(U1-PC2(ADC2)-Pad25)") (class "Default")
      (node (ref "U1") (pin "25") (pinfunction "PC2(ADC2)_25") (pintype "bidirectional"))
    )
    (net (code "225") (name "unconnected-(U1-PC3(ADC3)-Pad26)") (class "Default")
      (node (ref "U1") (pin "26") (pinfunction "PC3(ADC3)_26") (pintype "bidirectional"))
    )
    (net (code "226") (name "unconnected-(U1-PD2(INT0)-Pad32)") (class "Default")
      (node (ref "U1") (pin "32") (pinfunction "PD2(INT0)_32") (pintype "bidirectional"))
    )
    (net (code "227") (name "unconnected-(U1-PD5(T1)-Pad9)") (class "Default")
      (node (ref "U1") (pin "9") (pinfunction "PD5(T1)_9") (pintype "bidirectional"))
    )
    (net (code "228") (name "unconnected-(U1-PD6(AIN0)-Pad10)") (class "Default")
      (node (ref "U1") (pin "10") (pinfunction "PD6(AIN0)_10") (pintype "bidirectional"))
    )
    (net (code "229") (name "unconnected-(U1-PD7(AIN1)-Pad11)") (class "Default")
      (node (ref "U1") (pin "11") (pinfunction "PD7(AIN1)_11") (pintype "bidirectional"))
    )
    (net (code "230") (name "unconnected-(U2-ADC6-Pad19)") (class "Default")
      (node (ref "U2") (pin "19") (pinfunction "ADC6_19") (pintype "bidirectional"))
    )
    (net (code "231") (name "unconnected-(U2-ADC7-Pad22)") (class "Default")
      (node (ref "U2") (pin "22") (pinfunction "ADC7_22") (pintype "bidirectional"))
    )
    (net (code "232") (name "unconnected-(U2-PC1(ADC1)-Pad24)") (class "Default")
      (node (ref "U2") (pin "24") (pinfunction "PC1(ADC1)_24") (pintype "bidirectional"))
    )
    (net (code "233") (name "unconnected-(U2-PC2(ADC2)-Pad25)") (class "Default")
      (node (ref "U2") (pin "25") (pinfunction "PC2(ADC2)_25") (pintype "bidirectional"))
    )
    (net (code "234") (name "unconnected-(U2-PC3(ADC3)-Pad26)") (class "Default")
      (node (ref "U2") (pin "26") (pinfunction "PC3(ADC3)_26") (pintype "bidirectional"))
    )
    (net (code "235") (name "unconnected-(U4-GND-Pad6)") (class "Default")
      (node (ref "U4") (pin "6") (pinfunction "GND_6") (pintype "bidirectional"))
    )
    (net (code "236") (name "unconnected-(U4-NC-Pad1)") (class "Default")
      (node (ref "U4") (pin "1") (pinfunction "NC_1") (pintype "bidirectional"))
    )
    (net (code "237") (name "unconnected-(U4-RSV-Pad8)") (class "Default")
      (node (ref "U4") (pin "8") (pinfunction "RSV_8") (pintype "bidirectional"))
    )
    (net (code "238") (name "unconnected-(U4-SHIELD-PadCD1)") (class "Default")
      (node (ref "U4") (pin "CD1") (pinfunction "SHIELD_CD1") (pintype "bidirectional"))
    )
    (net (code "239") (name "unconnected-(U4-SHIELD-PadCD2)") (class "Default")
      (node (ref "U4") (pin "CD2") (pinfunction "SHIELD_CD2") (pintype "bidirectional"))
    )
  )
)
